# GEVCU-4_2.net
KiCad netlist of a schematic drawn in EAGLE
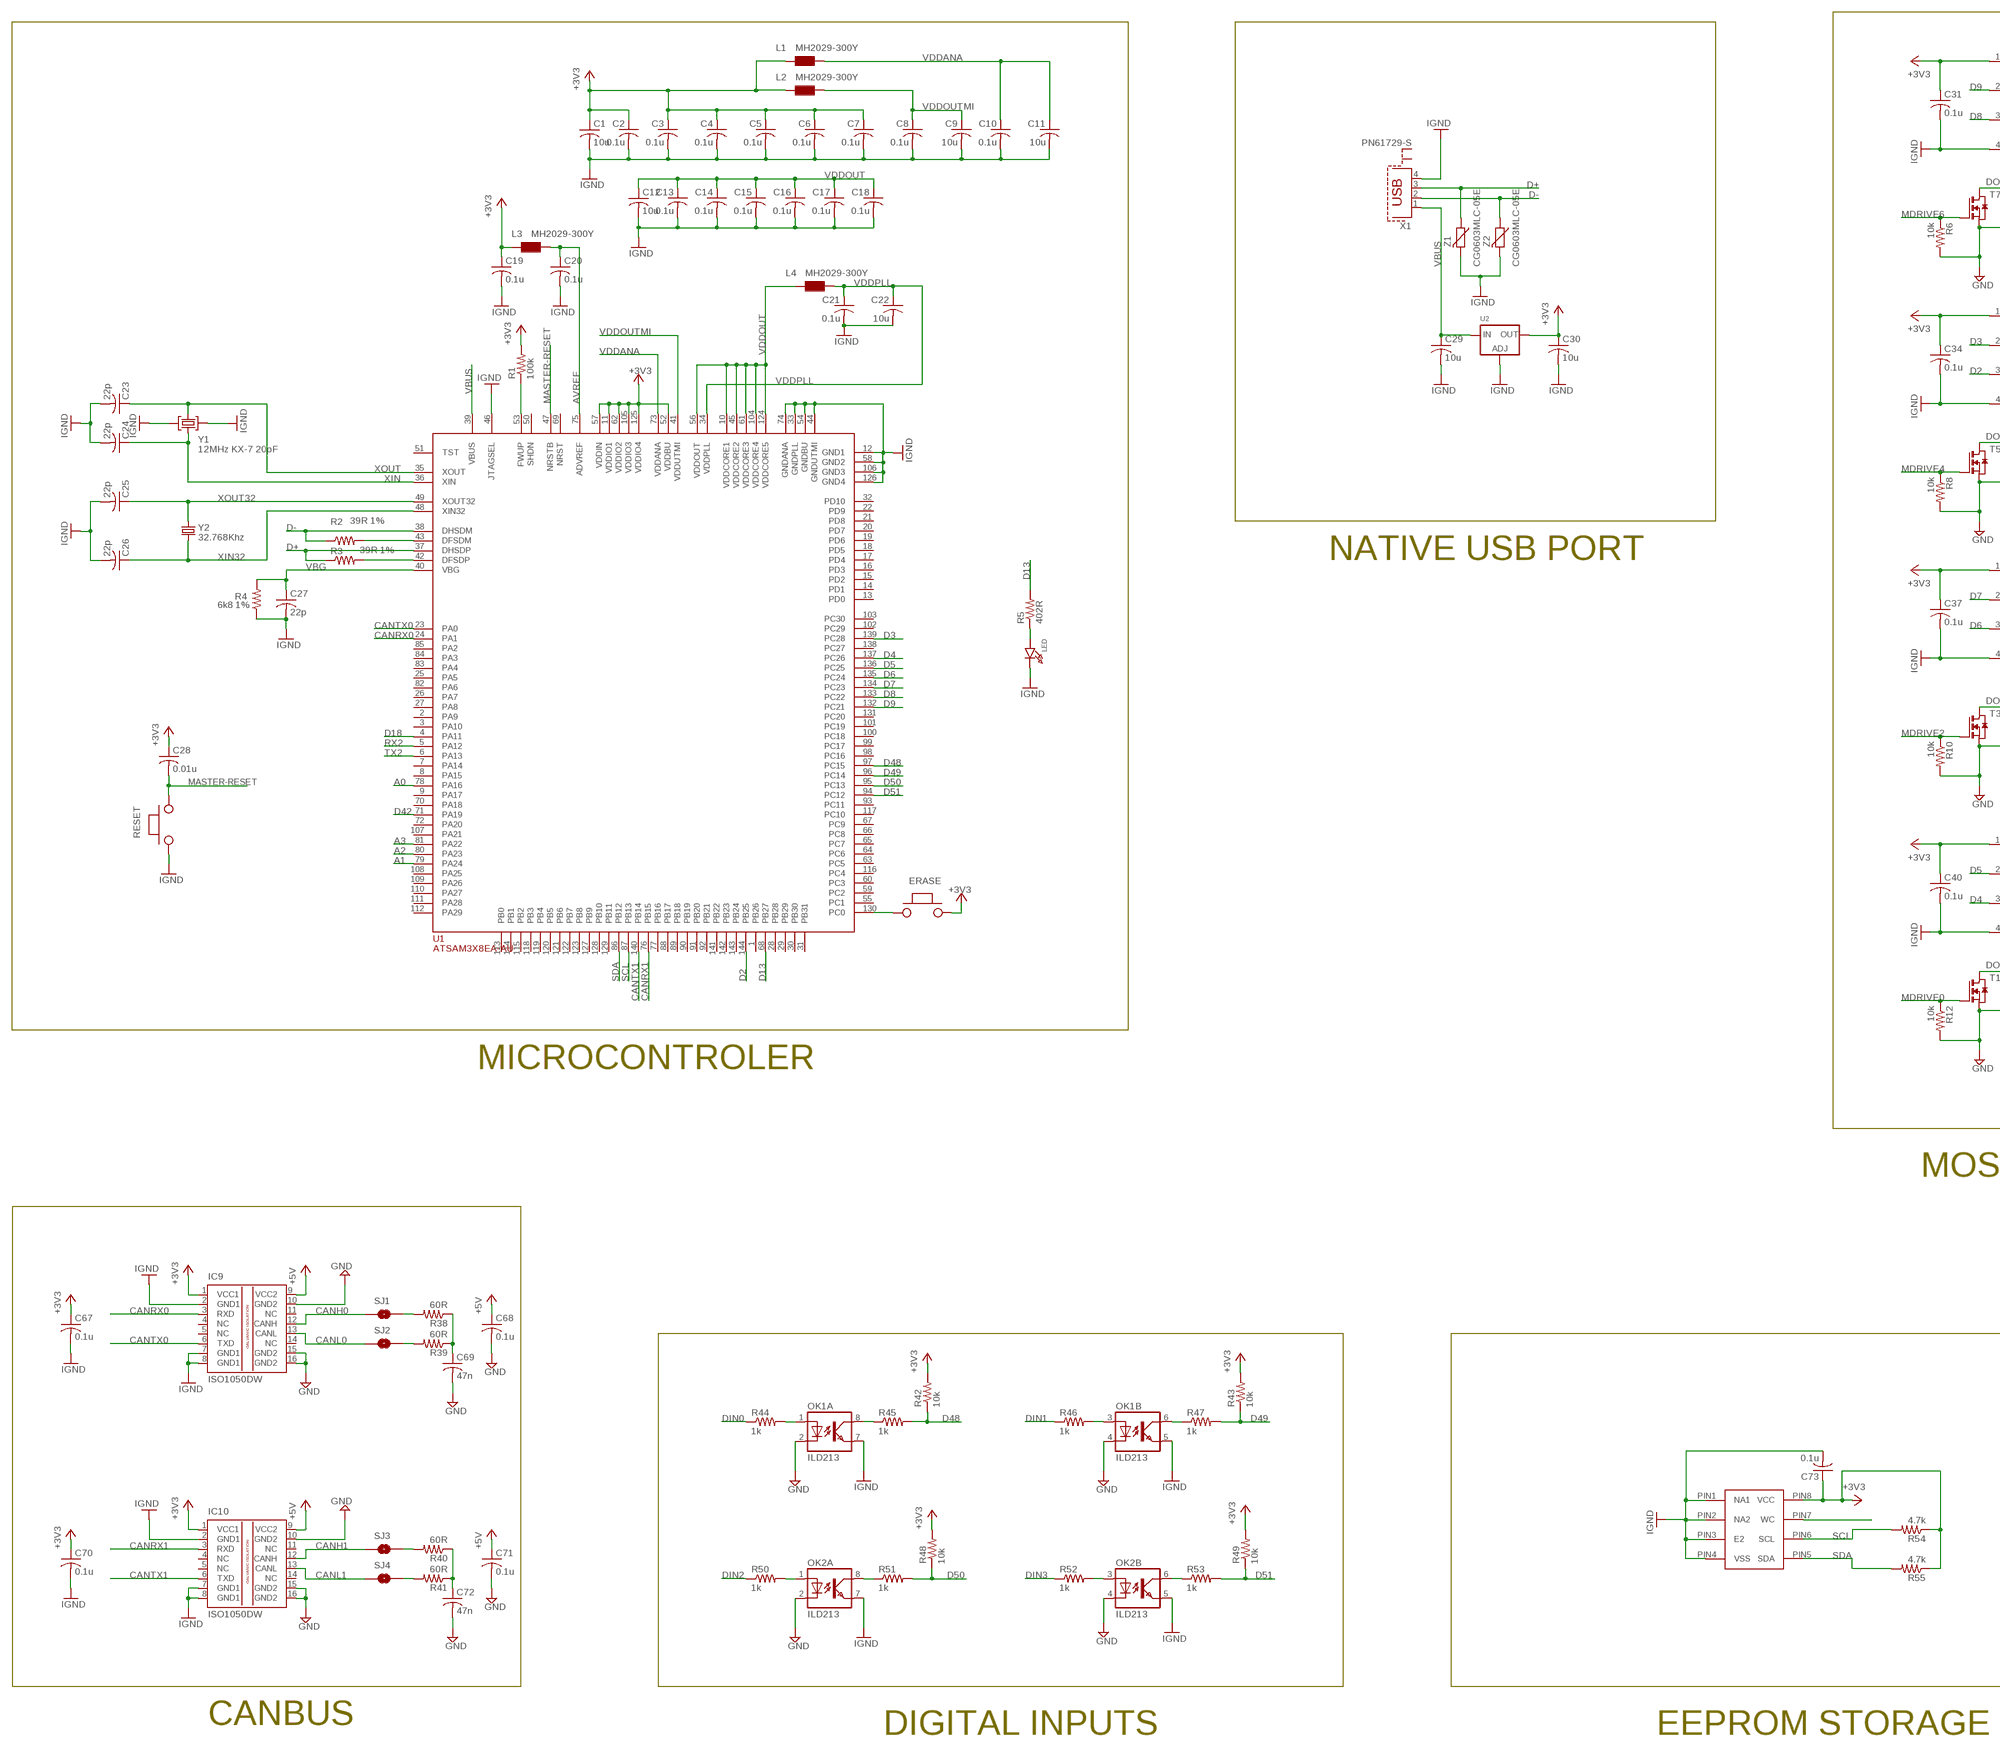
[diagram p0: schematic, sheet 1, part 1 of 2]
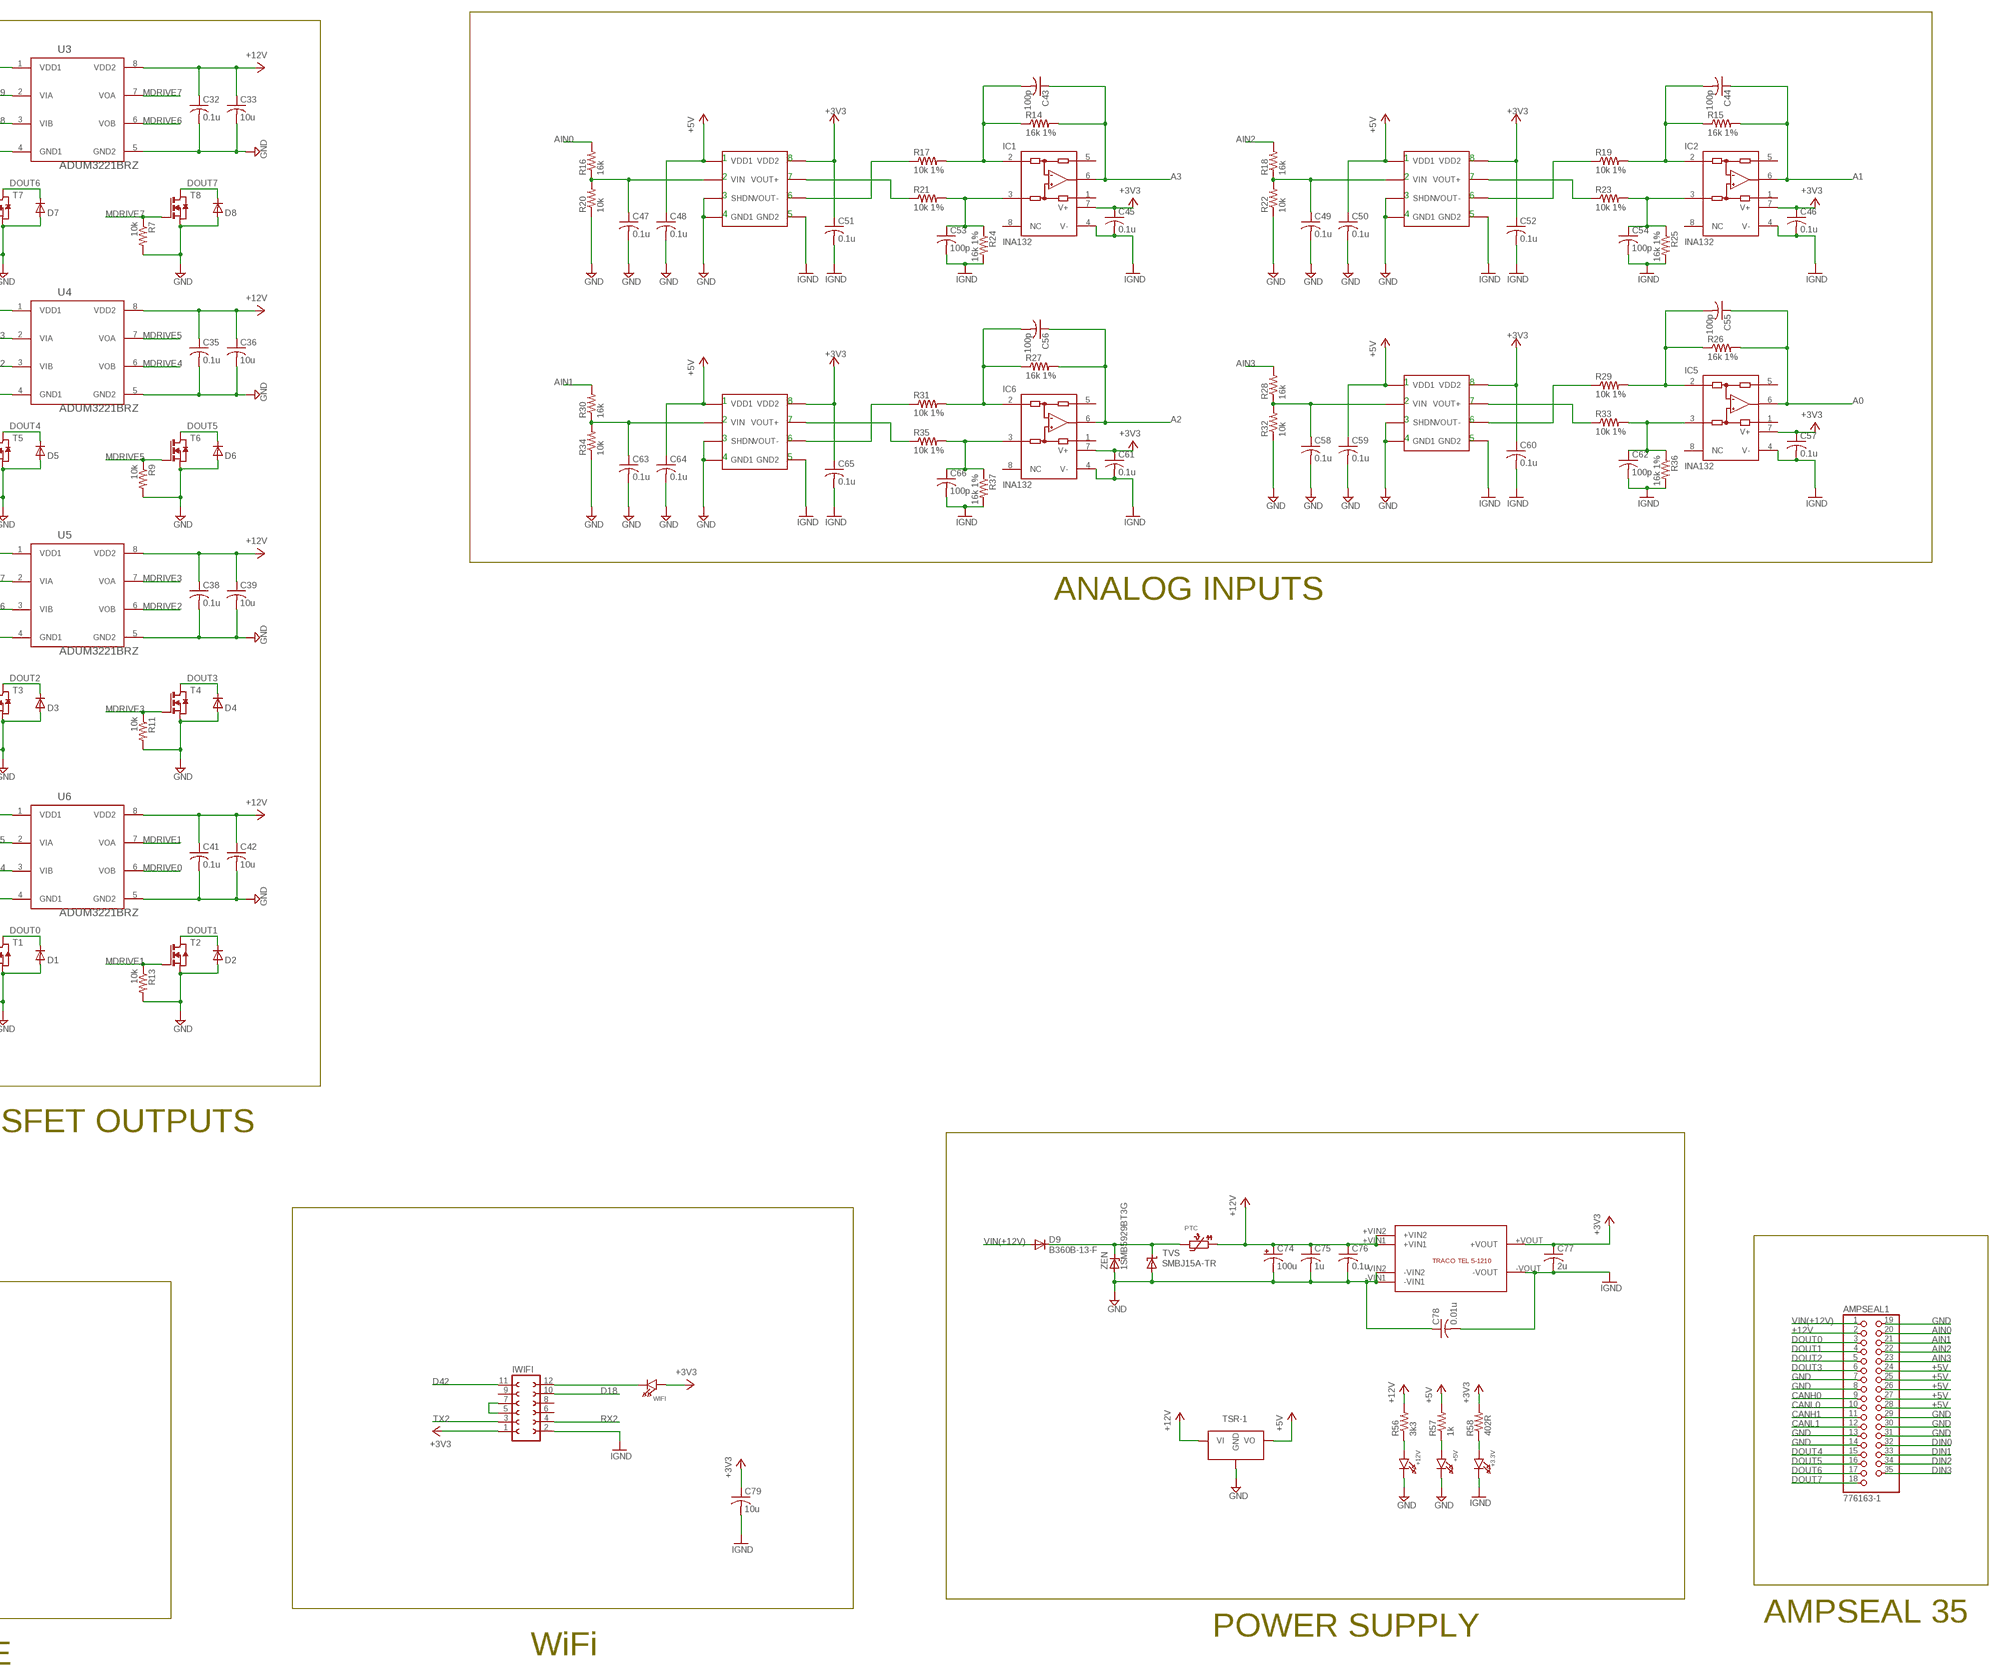
[diagram p1: schematic, sheet 1, part 2 of 2]

(export (version "E")
  (design (tool "Eeschema 10.0.6"))
  (components
    (comp (ref "+3.3V")
      (value "LED0805")
      (footprint "eagle-import:CHIPLED_0805")
      (libsource (lib "eagle-import") (part "LED0805"))
    )
    (comp (ref "+5V")
      (value "LED0805")
      (footprint "eagle-import:CHIPLED_0805")
      (libsource (lib "eagle-import") (part "LED0805"))
    )
    (comp (ref "+12V")
      (value "LED0805")
      (footprint "eagle-import:CHIPLED_0805")
      (libsource (lib "eagle-import") (part "LED0805"))
    )
    (comp (ref "AMPSEAL1")
      (value "776163-1")
      (footprint "eagle-import:AMPSEAL35")
      (libsource (lib "eagle-import") (part "AMPSEAL35"))
    )
    (comp (ref "C1")
      (value "10u")
      (footprint "eagle-import:C0805")
      (libsource (lib "eagle-import") (part "C-USC0805"))
    )
    (comp (ref "C2")
      (value "0.1u")
      (footprint "eagle-import:C0805")
      (libsource (lib "eagle-import") (part "C-USC0805"))
    )
    (comp (ref "C3")
      (value "0.1u")
      (footprint "eagle-import:C0805")
      (libsource (lib "eagle-import") (part "C-USC0805"))
    )
    (comp (ref "C4")
      (value "0.1u")
      (footprint "eagle-import:C0805")
      (libsource (lib "eagle-import") (part "C-USC0805"))
    )
    (comp (ref "C5")
      (value "0.1u")
      (footprint "eagle-import:C0805")
      (libsource (lib "eagle-import") (part "C-USC0805"))
    )
    (comp (ref "C6")
      (value "0.1u")
      (footprint "eagle-import:C0805")
      (libsource (lib "eagle-import") (part "C-USC0805"))
    )
    (comp (ref "C7")
      (value "0.1u")
      (footprint "eagle-import:C0805")
      (libsource (lib "eagle-import") (part "C-USC0805"))
    )
    (comp (ref "C8")
      (value "0.1u")
      (footprint "eagle-import:C0805")
      (libsource (lib "eagle-import") (part "C-USC0805"))
    )
    (comp (ref "C9")
      (value "10u")
      (footprint "eagle-import:C0805")
      (libsource (lib "eagle-import") (part "C-USC0805"))
    )
    (comp (ref "C10")
      (value "0.1u")
      (footprint "eagle-import:C0805")
      (libsource (lib "eagle-import") (part "C-USC0805"))
    )
    (comp (ref "C11")
      (value "10u")
      (footprint "eagle-import:C0805")
      (libsource (lib "eagle-import") (part "C-USC0805"))
    )
    (comp (ref "C12")
      (value "10u")
      (footprint "eagle-import:C0805")
      (libsource (lib "eagle-import") (part "C-USC0805"))
    )
    (comp (ref "C13")
      (value "0.1u")
      (footprint "eagle-import:C0805")
      (libsource (lib "eagle-import") (part "C-USC0805"))
    )
    (comp (ref "C14")
      (value "0.1u")
      (footprint "eagle-import:C0805")
      (libsource (lib "eagle-import") (part "C-USC0805"))
    )
    (comp (ref "C15")
      (value "0.1u")
      (footprint "eagle-import:C0805")
      (libsource (lib "eagle-import") (part "C-USC0805"))
    )
    (comp (ref "C16")
      (value "0.1u")
      (footprint "eagle-import:C0805")
      (libsource (lib "eagle-import") (part "C-USC0805"))
    )
    (comp (ref "C17")
      (value "0.1u")
      (footprint "eagle-import:C0805")
      (libsource (lib "eagle-import") (part "C-USC0805"))
    )
    (comp (ref "C18")
      (value "0.1u")
      (footprint "eagle-import:C0805")
      (libsource (lib "eagle-import") (part "C-USC0805"))
    )
    (comp (ref "C19")
      (value "0.1u")
      (footprint "eagle-import:C0805")
      (libsource (lib "eagle-import") (part "C-USC0805"))
    )
    (comp (ref "C20")
      (value "0.1u")
      (footprint "eagle-import:C0805")
      (libsource (lib "eagle-import") (part "C-USC0805"))
    )
    (comp (ref "C21")
      (value "0.1u")
      (footprint "eagle-import:C0805")
      (libsource (lib "eagle-import") (part "C-USC0805"))
    )
    (comp (ref "C22")
      (value "10u")
      (footprint "eagle-import:C0805")
      (libsource (lib "eagle-import") (part "C-USC0805"))
    )
    (comp (ref "C23")
      (value "22p")
      (footprint "eagle-import:C1206")
      (libsource (lib "eagle-import") (part "C-USC1206"))
    )
    (comp (ref "C24")
      (value "22p")
      (footprint "eagle-import:C1206")
      (libsource (lib "eagle-import") (part "C-USC1206"))
    )
    (comp (ref "C25")
      (value "22p")
      (footprint "eagle-import:C0805")
      (libsource (lib "eagle-import") (part "C-USC0805"))
    )
    (comp (ref "C26")
      (value "22p")
      (footprint "eagle-import:C0805")
      (libsource (lib "eagle-import") (part "C-USC0805"))
    )
    (comp (ref "C27")
      (value "22p")
      (footprint "eagle-import:C0805")
      (libsource (lib "eagle-import") (part "C-USC0805"))
    )
    (comp (ref "C28")
      (value "0.01u")
      (footprint "eagle-import:C0805")
      (libsource (lib "eagle-import") (part "C-USC0805"))
    )
    (comp (ref "C29")
      (value "10u")
      (footprint "eagle-import:C0805")
      (libsource (lib "eagle-import") (part "C-USC0805"))
    )
    (comp (ref "C30")
      (value "10u")
      (footprint "eagle-import:C0805")
      (libsource (lib "eagle-import") (part "C-USC0805"))
    )
    (comp (ref "C31")
      (value "0.1u")
      (footprint "eagle-import:C0805")
      (libsource (lib "eagle-import") (part "C-USC0805"))
    )
    (comp (ref "C32")
      (value "0.1u")
      (footprint "eagle-import:C0805")
      (libsource (lib "eagle-import") (part "C-USC0805"))
    )
    (comp (ref "C33")
      (value "10u")
      (footprint "eagle-import:C0805")
      (libsource (lib "eagle-import") (part "C-USC0805"))
    )
    (comp (ref "C34")
      (value "0.1u")
      (footprint "eagle-import:C0805")
      (libsource (lib "eagle-import") (part "C-USC0805"))
    )
    (comp (ref "C35")
      (value "0.1u")
      (footprint "eagle-import:C0805")
      (libsource (lib "eagle-import") (part "C-USC0805"))
    )
    (comp (ref "C36")
      (value "10u")
      (footprint "eagle-import:C0805")
      (libsource (lib "eagle-import") (part "C-USC0805"))
    )
    (comp (ref "C37")
      (value "0.1u")
      (footprint "eagle-import:C0805")
      (libsource (lib "eagle-import") (part "C-USC0805"))
    )
    (comp (ref "C38")
      (value "0.1u")
      (footprint "eagle-import:C0805")
      (libsource (lib "eagle-import") (part "C-USC0805"))
    )
    (comp (ref "C39")
      (value "10u")
      (footprint "eagle-import:C0805")
      (libsource (lib "eagle-import") (part "C-USC0805"))
    )
    (comp (ref "C40")
      (value "0.1u")
      (footprint "eagle-import:C0805")
      (libsource (lib "eagle-import") (part "C-USC0805"))
    )
    (comp (ref "C41")
      (value "0.1u")
      (footprint "eagle-import:C0805")
      (libsource (lib "eagle-import") (part "C-USC0805"))
    )
    (comp (ref "C42")
      (value "10u")
      (footprint "eagle-import:C0805")
      (libsource (lib "eagle-import") (part "C-USC0805"))
    )
    (comp (ref "C43")
      (value "100p")
      (footprint "eagle-import:C0805")
      (libsource (lib "eagle-import") (part "C-USC0805"))
    )
    (comp (ref "C44")
      (value "100p")
      (footprint "eagle-import:C0805")
      (libsource (lib "eagle-import") (part "C-USC0805"))
    )
    (comp (ref "C45")
      (value "0.1u")
      (footprint "eagle-import:C0805")
      (libsource (lib "eagle-import") (part "C-USC0805"))
    )
    (comp (ref "C46")
      (value "0.1u")
      (footprint "eagle-import:C0805")
      (libsource (lib "eagle-import") (part "C-USC0805"))
    )
    (comp (ref "C47")
      (value "0.1u")
      (footprint "eagle-import:C0805")
      (libsource (lib "eagle-import") (part "C-USC0805"))
    )
    (comp (ref "C48")
      (value "0.1u")
      (footprint "eagle-import:C1206")
      (libsource (lib "eagle-import") (part "C-USC1206"))
    )
    (comp (ref "C49")
      (value "0.1u")
      (footprint "eagle-import:C0805")
      (libsource (lib "eagle-import") (part "C-USC0805"))
    )
    (comp (ref "C50")
      (value "0.1u")
      (footprint "eagle-import:C1206")
      (libsource (lib "eagle-import") (part "C-USC1206"))
    )
    (comp (ref "C51")
      (value "0.1u")
      (footprint "eagle-import:C0805")
      (libsource (lib "eagle-import") (part "C-USC0805"))
    )
    (comp (ref "C52")
      (value "0.1u")
      (footprint "eagle-import:C0805")
      (libsource (lib "eagle-import") (part "C-USC0805"))
    )
    (comp (ref "C53")
      (value "100p")
      (footprint "eagle-import:C0805")
      (libsource (lib "eagle-import") (part "C-USC0805"))
    )
    (comp (ref "C54")
      (value "100p")
      (footprint "eagle-import:C0805")
      (libsource (lib "eagle-import") (part "C-USC0805"))
    )
    (comp (ref "C55")
      (value "100p")
      (footprint "eagle-import:C0805")
      (libsource (lib "eagle-import") (part "C-USC0805"))
    )
    (comp (ref "C56")
      (value "100p")
      (footprint "eagle-import:C0805")
      (libsource (lib "eagle-import") (part "C-USC0805"))
    )
    (comp (ref "C57")
      (value "0.1u")
      (footprint "eagle-import:C0805")
      (libsource (lib "eagle-import") (part "C-USC0805"))
    )
    (comp (ref "C58")
      (value "0.1u")
      (footprint "eagle-import:C0805")
      (libsource (lib "eagle-import") (part "C-USC0805"))
    )
    (comp (ref "C59")
      (value "0.1u")
      (footprint "eagle-import:C1206")
      (libsource (lib "eagle-import") (part "C-USC1206"))
    )
    (comp (ref "C60")
      (value "0.1u")
      (footprint "eagle-import:C0805")
      (libsource (lib "eagle-import") (part "C-USC0805"))
    )
    (comp (ref "C61")
      (value "0.1u")
      (footprint "eagle-import:C0805")
      (libsource (lib "eagle-import") (part "C-USC0805"))
    )
    (comp (ref "C62")
      (value "100p")
      (footprint "eagle-import:C0805")
      (libsource (lib "eagle-import") (part "C-USC0805"))
    )
    (comp (ref "C63")
      (value "0.1u")
      (footprint "eagle-import:C0805")
      (libsource (lib "eagle-import") (part "C-USC0805"))
    )
    (comp (ref "C64")
      (value "0.1u")
      (footprint "eagle-import:C1206")
      (libsource (lib "eagle-import") (part "C-USC1206"))
    )
    (comp (ref "C65")
      (value "0.1u")
      (footprint "eagle-import:C0805")
      (libsource (lib "eagle-import") (part "C-USC0805"))
    )
    (comp (ref "C66")
      (value "100p")
      (footprint "eagle-import:C0805")
      (libsource (lib "eagle-import") (part "C-USC0805"))
    )
    (comp (ref "C67")
      (value "0.1u")
      (footprint "eagle-import:C0805")
      (libsource (lib "eagle-import") (part "C-USC0805"))
    )
    (comp (ref "C68")
      (value "0.1u")
      (footprint "eagle-import:C0805")
      (libsource (lib "eagle-import") (part "C-USC0805"))
    )
    (comp (ref "C69")
      (value "47n")
      (footprint "eagle-import:C0805")
      (libsource (lib "eagle-import") (part "C-USC0805"))
    )
    (comp (ref "C70")
      (value "0.1u")
      (footprint "eagle-import:C0805")
      (libsource (lib "eagle-import") (part "C-USC0805"))
    )
    (comp (ref "C71")
      (value "0.1u")
      (footprint "eagle-import:C0805")
      (libsource (lib "eagle-import") (part "C-USC0805"))
    )
    (comp (ref "C72")
      (value "47n")
      (footprint "eagle-import:C0805")
      (libsource (lib "eagle-import") (part "C-USC0805"))
    )
    (comp (ref "C73")
      (value "0.1u")
      (footprint "eagle-import:C0805")
      (libsource (lib "eagle-import") (part "C-USC0805"))
    )
    (comp (ref "C74")
      (value "100u")
      (footprint "eagle-import:E2,5-6")
      (libsource (lib "eagle-import") (part "CPOL-USE2.5-6"))
    )
    (comp (ref "C75")
      (value "1u")
      (footprint "eagle-import:C0805")
      (libsource (lib "eagle-import") (part "C-USC0805"))
    )
    (comp (ref "C76")
      (value "0.1u")
      (footprint "eagle-import:C0805")
      (libsource (lib "eagle-import") (part "C-USC0805"))
    )
    (comp (ref "C77")
      (value "2u")
      (footprint "eagle-import:C0805")
      (libsource (lib "eagle-import") (part "C-USC0805"))
    )
    (comp (ref "C78")
      (value "0.01u")
      (footprint "eagle-import:C1812")
      (libsource (lib "eagle-import") (part "C-USC1812"))
    )
    (comp (ref "C79")
      (value "10u")
      (footprint "eagle-import:C0805")
      (libsource (lib "eagle-import") (part "C-USC0805"))
    )
    (comp (ref "D1")
      (value "MBR0520LT")
      (footprint "eagle-import:SOD123")
      (libsource (lib "eagle-import") (part "MBR0520LT"))
    )
    (comp (ref "D2")
      (value "MBR0520LT")
      (footprint "eagle-import:SOD123")
      (libsource (lib "eagle-import") (part "MBR0520LT"))
    )
    (comp (ref "D3")
      (value "MBR0520LT")
      (footprint "eagle-import:SOD123")
      (libsource (lib "eagle-import") (part "MBR0520LT"))
    )
    (comp (ref "D4")
      (value "MBR0520LT")
      (footprint "eagle-import:SOD123")
      (libsource (lib "eagle-import") (part "MBR0520LT"))
    )
    (comp (ref "D5")
      (value "MBR0520LT")
      (footprint "eagle-import:SOD123")
      (libsource (lib "eagle-import") (part "MBR0520LT"))
    )
    (comp (ref "D6")
      (value "MBR0520LT")
      (footprint "eagle-import:SOD123")
      (libsource (lib "eagle-import") (part "MBR0520LT"))
    )
    (comp (ref "D7")
      (value "MBR0520LT")
      (footprint "eagle-import:SOD123")
      (libsource (lib "eagle-import") (part "MBR0520LT"))
    )
    (comp (ref "D8")
      (value "MBR0520LT")
      (footprint "eagle-import:SOD123")
      (libsource (lib "eagle-import") (part "MBR0520LT"))
    )
    (comp (ref "D9")
      (value "B360B-13-F")
      (footprint "eagle-import:SMB")
      (libsource (lib "eagle-import") (part "DIODE-SMB"))
    )
    (comp (ref "ERASE")
      (value "PUCHBUTTON")
      (footprint "eagle-import:PUCHBUTTON")
      (libsource (lib "eagle-import") (part "PUCHBUTTON"))
    )
    (comp (ref "IC1")
      (value "INA132")
      (footprint "eagle-import:SO08")
      (fields (field (name "MF") "TEXAS INSTRUMENTS") (field (name "MPN") "INA105KU"))
      (libsource (lib "eagle-import") (part "INA105U"))
    )
    (comp (ref "IC2")
      (value "INA132")
      (footprint "eagle-import:SO08")
      (fields (field (name "MF") "TEXAS INSTRUMENTS") (field (name "MPN") "INA105KU"))
      (libsource (lib "eagle-import") (part "INA105U"))
    )
    (comp (ref "IC3")
      (value "CK_CUSTOM_ACPL-C87A-000E")
      (footprint "eagle-import:CK_CUSTOM_SO8-WIDE")
      (libsource (lib "eagle-import") (part "CK_CUSTOM_ACPL-C87A-000E"))
    )
    (comp (ref "IC4")
      (value "CK_CUSTOM_ACPL-C87A-000E")
      (footprint "eagle-import:CK_CUSTOM_SO8-WIDE")
      (libsource (lib "eagle-import") (part "CK_CUSTOM_ACPL-C87A-000E"))
    )
    (comp (ref "IC5")
      (value "INA132")
      (footprint "eagle-import:SO08")
      (fields (field (name "MF") "TEXAS INSTRUMENTS") (field (name "MPN") "INA105KU"))
      (libsource (lib "eagle-import") (part "INA105U"))
    )
    (comp (ref "IC6")
      (value "INA132")
      (footprint "eagle-import:SO08")
      (fields (field (name "MF") "TEXAS INSTRUMENTS") (field (name "MPN") "INA105KU"))
      (libsource (lib "eagle-import") (part "INA105U"))
    )
    (comp (ref "IC7")
      (value "CK_CUSTOM_ACPL-C87A-000E")
      (footprint "eagle-import:CK_CUSTOM_SO8-WIDE")
      (libsource (lib "eagle-import") (part "CK_CUSTOM_ACPL-C87A-000E"))
    )
    (comp (ref "IC8")
      (value "CK_CUSTOM_ACPL-C87A-000E")
      (footprint "eagle-import:CK_CUSTOM_SO8-WIDE")
      (libsource (lib "eagle-import") (part "CK_CUSTOM_ACPL-C87A-000E"))
    )
    (comp (ref "IC9")
      (value "ISO1050DW")
      (footprint "eagle-import:DUB-R-PDSO-G8")
      (libsource (lib "eagle-import") (part "ISO1050DUB"))
    )
    (comp (ref "IC10")
      (value "ISO1050DW")
      (footprint "eagle-import:DUB-R-PDSO-G8")
      (libsource (lib "eagle-import") (part "ISO1050DUB"))
    )
    (comp (ref "IWIFI")
      (value "FE06-2")
      (footprint "eagle-import:FE06-2")
      (libsource (lib "eagle-import") (part "FE06-2"))
    )
    (comp (ref "L1")
      (value "MH2029-300Y")
      (footprint "eagle-import:0805")
      (libsource (lib "eagle-import") (part "WE-CBF_0805"))
    )
    (comp (ref "L2")
      (value "MH2029-300Y")
      (footprint "eagle-import:0805")
      (libsource (lib "eagle-import") (part "WE-CBF_0805"))
    )
    (comp (ref "L3")
      (value "MH2029-300Y")
      (footprint "eagle-import:0805")
      (libsource (lib "eagle-import") (part "WE-CBF_0805"))
    )
    (comp (ref "L4")
      (value "MH2029-300Y")
      (footprint "eagle-import:0805")
      (libsource (lib "eagle-import") (part "WE-CBF_0805"))
    )
    (comp (ref "LED")
      (value "LED0805")
      (footprint "eagle-import:CHIPLED_0805")
      (libsource (lib "eagle-import") (part "LED0805"))
    )
    (comp (ref "OK1")
      (value "ILD213")
      (footprint "eagle-import:SOIC08")
      (fields (field (name "MF") "VISHAY/TELEFUNKEN") (field (name "MPN") "ILD213T"))
      (libsource (lib "eagle-import") (part "ILD213"))
    )
    (comp (ref "OK2")
      (value "ILD213")
      (footprint "eagle-import:SOIC08")
      (fields (field (name "MF") "VISHAY/TELEFUNKEN") (field (name "MPN") "ILD213T"))
      (libsource (lib "eagle-import") (part "ILD213"))
    )
    (comp (ref "PTC")
      (value "PTC1812")
      (footprint "eagle-import:PTC1812")
      (libsource (lib "eagle-import") (part "PTC1812"))
    )
    (comp (ref "R1")
      (value "100k")
      (footprint "eagle-import:R0805")
      (libsource (lib "eagle-import") (part "R-US_R0805"))
    )
    (comp (ref "R2")
      (value "39R 1%")
      (footprint "eagle-import:R0805")
      (libsource (lib "eagle-import") (part "R-US_R0805"))
    )
    (comp (ref "R3")
      (value "39R 1%")
      (footprint "eagle-import:R0805")
      (libsource (lib "eagle-import") (part "R-US_R0805"))
    )
    (comp (ref "R4")
      (value "6k8 1%")
      (footprint "eagle-import:R0805")
      (libsource (lib "eagle-import") (part "R-US_R0805"))
    )
    (comp (ref "R5")
      (value "402R")
      (footprint "eagle-import:R0805")
      (libsource (lib "eagle-import") (part "R-US_R0805"))
    )
    (comp (ref "R6")
      (value "10k")
      (footprint "eagle-import:R0805")
      (libsource (lib "eagle-import") (part "R-US_R0805"))
    )
    (comp (ref "R7")
      (value "10k")
      (footprint "eagle-import:R0805")
      (libsource (lib "eagle-import") (part "R-US_R0805"))
    )
    (comp (ref "R8")
      (value "10k")
      (footprint "eagle-import:R0805")
      (libsource (lib "eagle-import") (part "R-US_R0805"))
    )
    (comp (ref "R9")
      (value "10k")
      (footprint "eagle-import:R0805")
      (libsource (lib "eagle-import") (part "R-US_R0805"))
    )
    (comp (ref "R10")
      (value "10k")
      (footprint "eagle-import:R0805")
      (libsource (lib "eagle-import") (part "R-US_R0805"))
    )
    (comp (ref "R11")
      (value "10k")
      (footprint "eagle-import:R0805")
      (libsource (lib "eagle-import") (part "R-US_R0805"))
    )
    (comp (ref "R12")
      (value "10k")
      (footprint "eagle-import:R0805")
      (libsource (lib "eagle-import") (part "R-US_R0805"))
    )
    (comp (ref "R13")
      (value "10k")
      (footprint "eagle-import:R0805")
      (libsource (lib "eagle-import") (part "R-US_R0805"))
    )
    (comp (ref "R14")
      (value "16k 1%")
      (footprint "eagle-import:R0805")
      (libsource (lib "eagle-import") (part "R-US_R0805"))
    )
    (comp (ref "R15")
      (value "16k 1%")
      (footprint "eagle-import:R0805")
      (libsource (lib "eagle-import") (part "R-US_R0805"))
    )
    (comp (ref "R16")
      (value "16k")
      (footprint "eagle-import:R0805")
      (libsource (lib "eagle-import") (part "R-US_R0805"))
    )
    (comp (ref "R17")
      (value "10k 1%")
      (footprint "eagle-import:R0805")
      (libsource (lib "eagle-import") (part "R-US_R0805"))
    )
    (comp (ref "R18")
      (value "16k")
      (footprint "eagle-import:R0805")
      (libsource (lib "eagle-import") (part "R-US_R0805"))
    )
    (comp (ref "R19")
      (value "10k 1%")
      (footprint "eagle-import:R0805")
      (libsource (lib "eagle-import") (part "R-US_R0805"))
    )
    (comp (ref "R20")
      (value "10k")
      (footprint "eagle-import:R0805")
      (libsource (lib "eagle-import") (part "R-US_R0805"))
    )
    (comp (ref "R21")
      (value "10k 1%")
      (footprint "eagle-import:R0805")
      (libsource (lib "eagle-import") (part "R-US_R0805"))
    )
    (comp (ref "R22")
      (value "10k")
      (footprint "eagle-import:R0805")
      (libsource (lib "eagle-import") (part "R-US_R0805"))
    )
    (comp (ref "R23")
      (value "10k 1%")
      (footprint "eagle-import:R0805")
      (libsource (lib "eagle-import") (part "R-US_R0805"))
    )
    (comp (ref "R24")
      (value "16k 1%")
      (footprint "eagle-import:R0805")
      (libsource (lib "eagle-import") (part "R-US_R0805"))
    )
    (comp (ref "R25")
      (value "16k 1%")
      (footprint "eagle-import:R0805")
      (libsource (lib "eagle-import") (part "R-US_R0805"))
    )
    (comp (ref "R26")
      (value "16k 1%")
      (footprint "eagle-import:R0805")
      (libsource (lib "eagle-import") (part "R-US_R0805"))
    )
    (comp (ref "R27")
      (value "16k 1%")
      (footprint "eagle-import:R0805")
      (libsource (lib "eagle-import") (part "R-US_R0805"))
    )
    (comp (ref "R28")
      (value "16k")
      (footprint "eagle-import:R0805")
      (libsource (lib "eagle-import") (part "R-US_R0805"))
    )
    (comp (ref "R29")
      (value "10k 1%")
      (footprint "eagle-import:R0805")
      (libsource (lib "eagle-import") (part "R-US_R0805"))
    )
    (comp (ref "R30")
      (value "16k")
      (footprint "eagle-import:R0805")
      (libsource (lib "eagle-import") (part "R-US_R0805"))
    )
    (comp (ref "R31")
      (value "10k 1%")
      (footprint "eagle-import:R0805")
      (libsource (lib "eagle-import") (part "R-US_R0805"))
    )
    (comp (ref "R32")
      (value "10k")
      (footprint "eagle-import:R0805")
      (libsource (lib "eagle-import") (part "R-US_R0805"))
    )
    (comp (ref "R33")
      (value "10k 1%")
      (footprint "eagle-import:R0805")
      (libsource (lib "eagle-import") (part "R-US_R0805"))
    )
    (comp (ref "R34")
      (value "10k")
      (footprint "eagle-import:R0805")
      (libsource (lib "eagle-import") (part "R-US_R0805"))
    )
    (comp (ref "R35")
      (value "10k 1%")
      (footprint "eagle-import:R0805")
      (libsource (lib "eagle-import") (part "R-US_R0805"))
    )
    (comp (ref "R36")
      (value "16k 1%")
      (footprint "eagle-import:R0805")
      (libsource (lib "eagle-import") (part "R-US_R0805"))
    )
    (comp (ref "R37")
      (value "16k 1%")
      (footprint "eagle-import:R0805")
      (libsource (lib "eagle-import") (part "R-US_R0805"))
    )
    (comp (ref "R38")
      (value "60R")
      (footprint "eagle-import:R0805")
      (libsource (lib "eagle-import") (part "R-US_R0805"))
    )
    (comp (ref "R39")
      (value "60R")
      (footprint "eagle-import:R0805")
      (libsource (lib "eagle-import") (part "R-US_R0805"))
    )
    (comp (ref "R40")
      (value "60R")
      (footprint "eagle-import:R0805")
      (libsource (lib "eagle-import") (part "R-US_R0805"))
    )
    (comp (ref "R41")
      (value "60R")
      (footprint "eagle-import:R0805")
      (libsource (lib "eagle-import") (part "R-US_R0805"))
    )
    (comp (ref "R42")
      (value "10k")
      (footprint "eagle-import:R0805")
      (libsource (lib "eagle-import") (part "R-US_R0805"))
    )
    (comp (ref "R43")
      (value "10k")
      (footprint "eagle-import:R0805")
      (libsource (lib "eagle-import") (part "R-US_R0805"))
    )
    (comp (ref "R44")
      (value "1k")
      (footprint "eagle-import:R0805")
      (libsource (lib "eagle-import") (part "R-US_R0805"))
    )
    (comp (ref "R45")
      (value "1k")
      (footprint "eagle-import:R0805")
      (libsource (lib "eagle-import") (part "R-US_R0805"))
    )
    (comp (ref "R46")
      (value "1k")
      (footprint "eagle-import:R0805")
      (libsource (lib "eagle-import") (part "R-US_R0805"))
    )
    (comp (ref "R47")
      (value "1k")
      (footprint "eagle-import:R0805")
      (libsource (lib "eagle-import") (part "R-US_R0805"))
    )
    (comp (ref "R48")
      (value "10k")
      (footprint "eagle-import:R0805")
      (libsource (lib "eagle-import") (part "R-US_R0805"))
    )
    (comp (ref "R49")
      (value "10k")
      (footprint "eagle-import:R0805")
      (libsource (lib "eagle-import") (part "R-US_R0805"))
    )
    (comp (ref "R50")
      (value "1k")
      (footprint "eagle-import:R0805")
      (libsource (lib "eagle-import") (part "R-US_R0805"))
    )
    (comp (ref "R51")
      (value "1k")
      (footprint "eagle-import:R0805")
      (libsource (lib "eagle-import") (part "R-US_R0805"))
    )
    (comp (ref "R52")
      (value "1k")
      (footprint "eagle-import:R0805")
      (libsource (lib "eagle-import") (part "R-US_R0805"))
    )
    (comp (ref "R53")
      (value "1k")
      (footprint "eagle-import:R0805")
      (libsource (lib "eagle-import") (part "R-US_R0805"))
    )
    (comp (ref "R54")
      (value "4.7k")
      (footprint "eagle-import:R0805")
      (libsource (lib "eagle-import") (part "R-US_R0805"))
    )
    (comp (ref "R55")
      (value "4.7k")
      (footprint "eagle-import:R0805")
      (libsource (lib "eagle-import") (part "R-US_R0805"))
    )
    (comp (ref "R56")
      (value "3k3")
      (footprint "eagle-import:R0805")
      (libsource (lib "eagle-import") (part "R-US_R0805"))
    )
    (comp (ref "R57")
      (value "1k")
      (footprint "eagle-import:R0805")
      (libsource (lib "eagle-import") (part "R-US_R0805"))
    )
    (comp (ref "R58")
      (value "402R")
      (footprint "eagle-import:R0805")
      (libsource (lib "eagle-import") (part "R-US_R0805"))
    )
    (comp (ref "RESET")
      (value "PUCHBUTTON")
      (footprint "eagle-import:PUCHBUTTON")
      (libsource (lib "eagle-import") (part "PUCHBUTTON"))
    )
    (comp (ref "SJ1")
      (value "SOLDERJUMPERNO")
      (footprint "eagle-import:SJ_2S-NO")
      (libsource (lib "eagle-import") (part "SOLDERJUMPERNO"))
    )
    (comp (ref "SJ2")
      (value "SOLDERJUMPERNO")
      (footprint "eagle-import:SJ_2S-NO")
      (libsource (lib "eagle-import") (part "SOLDERJUMPERNO"))
    )
    (comp (ref "SJ3")
      (value "SOLDERJUMPERNO")
      (footprint "eagle-import:SJ_2S-NO")
      (libsource (lib "eagle-import") (part "SOLDERJUMPERNO"))
    )
    (comp (ref "SJ4")
      (value "SOLDERJUMPERNO")
      (footprint "eagle-import:SJ_2S-NO")
      (libsource (lib "eagle-import") (part "SOLDERJUMPERNO"))
    )
    (comp (ref "T1")
      (value "NMOSSOT223")
      (footprint "eagle-import:SOT223")
      (libsource (lib "eagle-import") (part "NMOSSOT223"))
    )
    (comp (ref "T2")
      (value "NMOSSOT223")
      (footprint "eagle-import:SOT223")
      (libsource (lib "eagle-import") (part "NMOSSOT223"))
    )
    (comp (ref "T3")
      (value "NMOSSOT223")
      (footprint "eagle-import:SOT223")
      (libsource (lib "eagle-import") (part "NMOSSOT223"))
    )
    (comp (ref "T4")
      (value "NMOSSOT223")
      (footprint "eagle-import:SOT223")
      (libsource (lib "eagle-import") (part "NMOSSOT223"))
    )
    (comp (ref "T5")
      (value "NMOSSOT223")
      (footprint "eagle-import:SOT223")
      (libsource (lib "eagle-import") (part "NMOSSOT223"))
    )
    (comp (ref "T6")
      (value "NMOSSOT223")
      (footprint "eagle-import:SOT223")
      (libsource (lib "eagle-import") (part "NMOSSOT223"))
    )
    (comp (ref "T7")
      (value "NMOSSOT223")
      (footprint "eagle-import:SOT223")
      (libsource (lib "eagle-import") (part "NMOSSOT223"))
    )
    (comp (ref "T8")
      (value "NMOSSOT223")
      (footprint "eagle-import:SOT223")
      (libsource (lib "eagle-import") (part "NMOSSOT223"))
    )
    (comp (ref "TVS")
      (value "SMBJ15A-TR")
      (footprint "eagle-import:SMBJ")
      (libsource (lib "eagle-import") (part "SUPPRESSOR-SMBJ"))
    )
    (comp (ref "U1")
      (value "ATSAM3X8EA-AU")
      (footprint "eagle-import:LQFP144")
      (libsource (lib "eagle-import") (part "ATSAM3X/AAU"))
    )
    (comp (ref "U2")
      (value "LM1117SOT223-WAVE")
      (footprint "eagle-import:SOT223-W")
      (libsource (lib "eagle-import") (part "LM1117SOT223-WAVE"))
    )
    (comp (ref "U3")
      (value "ADUM3221BRZ")
      (footprint "eagle-import:SOIC127P600X175-8N")
      (libsource (lib "eagle-import") (part "ADUM3221BRZ"))
    )
    (comp (ref "U4")
      (value "ADUM3221BRZ")
      (footprint "eagle-import:SOIC127P600X175-8N")
      (libsource (lib "eagle-import") (part "ADUM3221BRZ"))
    )
    (comp (ref "U5")
      (value "ADUM3221BRZ")
      (footprint "eagle-import:SOIC127P600X175-8N")
      (libsource (lib "eagle-import") (part "ADUM3221BRZ"))
    )
    (comp (ref "U6")
      (value "ADUM3221BRZ")
      (footprint "eagle-import:SOIC127P600X175-8N")
      (libsource (lib "eagle-import") (part "ADUM3221BRZ"))
    )
    (comp (ref "U7")
      (value "CK_CUSTOM_M24M02-DRMN6TP")
      (footprint "eagle-import:CK_CUSTOM_SOIC8")
      (libsource (lib "eagle-import") (part "CK_CUSTOM_M24M02-DRMN6TP"))
    )
    (comp (ref "U8")
      (value "TRACO")
      (footprint "eagle-import:TRACO")
      (libsource (lib "eagle-import") (part "TRACO"))
    )
    (comp (ref "U9")
      (value "TSR-1")
      (footprint "eagle-import:TSR-1")
      (libsource (lib "eagle-import") (part "TSR-1"))
    )
    (comp (ref "WIFI")
      (value "LED0805")
      (footprint "eagle-import:CHIPLED_0805")
      (libsource (lib "eagle-import") (part "LED0805"))
    )
    (comp (ref "X1")
      (value "PN61729-S")
      (footprint "eagle-import:PN61729-S")
      (libsource (lib "eagle-import") (part "PN61729-S"))
    )
    (comp (ref "Y1")
      (value "12MHz KX-7 20pF")
      (footprint "eagle-import:CRYSTAL-3.2-2.5")
      (libsource (lib "eagle-import") (part "CRYSTAL-3.2-2.5"))
    )
    (comp (ref "Y2")
      (value "32.768Khz")
      (footprint "eagle-import:ARDUINO_WIFI_SHIELD_V018_TG_RESONATOR_EPSON_FC_145")
      (libsource (lib "eagle-import") (part "ARDUINO_WIFI_SHIELD_V018_TG_RESONATOR_EPSON_FC_145"))
    )
    (comp (ref "Z1")
      (value "CG0603MLC-05E")
      (footprint "eagle-import:CT_CN0603")
      (libsource (lib "eagle-import") (part "VARISTORCN0603"))
    )
    (comp (ref "Z2")
      (value "CG0603MLC-05E")
      (footprint "eagle-import:CT_CN0603")
      (libsource (lib "eagle-import") (part "VARISTORCN0603"))
    )
    (comp (ref "ZEN")
      (value "1SMB5929BT3G")
      (footprint "eagle-import:SMB")
      (libsource (lib "eagle-import") (part "ZENER-DIODESMB"))
    )
  )
  (nets
    (net (code "1") (name "+3V3") (class "Default")
      (node (ref "C1") (pin "1") (pinfunction "1_1") (pintype "passive"))
      (node (ref "C19") (pin "1") (pinfunction "1_1") (pintype "passive"))
      (node (ref "C2") (pin "1") (pinfunction "1_1") (pintype "passive"))
      (node (ref "C28") (pin "1") (pinfunction "1_1") (pintype "passive"))
      (node (ref "C3") (pin "1") (pinfunction "1_1") (pintype "passive"))
      (node (ref "C30") (pin "1") (pinfunction "1_1") (pintype "passive"))
      (node (ref "C31") (pin "1") (pinfunction "1_1") (pintype "passive"))
      (node (ref "C34") (pin "1") (pinfunction "1_1") (pintype "passive"))
      (node (ref "C37") (pin "1") (pinfunction "1_1") (pintype "passive"))
      (node (ref "C4") (pin "1") (pinfunction "1_1") (pintype "passive"))
      (node (ref "C40") (pin "1") (pinfunction "1_1") (pintype "passive"))
      (node (ref "C45") (pin "1") (pinfunction "1_1") (pintype "passive"))
      (node (ref "C46") (pin "1") (pinfunction "1_1") (pintype "passive"))
      (node (ref "C5") (pin "1") (pinfunction "1_1") (pintype "passive"))
      (node (ref "C51") (pin "1") (pinfunction "1_1") (pintype "passive"))
      (node (ref "C52") (pin "1") (pinfunction "1_1") (pintype "passive"))
      (node (ref "C57") (pin "1") (pinfunction "1_1") (pintype "passive"))
      (node (ref "C6") (pin "1") (pinfunction "1_1") (pintype "passive"))
      (node (ref "C60") (pin "1") (pinfunction "1_1") (pintype "passive"))
      (node (ref "C61") (pin "1") (pinfunction "1_1") (pintype "passive"))
      (node (ref "C65") (pin "1") (pinfunction "1_1") (pintype "passive"))
      (node (ref "C67") (pin "1") (pinfunction "1_1") (pintype "passive"))
      (node (ref "C7") (pin "1") (pinfunction "1_1") (pintype "passive"))
      (node (ref "C70") (pin "1") (pinfunction "1_1") (pintype "passive"))
      (node (ref "C73") (pin "1") (pinfunction "1_1") (pintype "passive"))
      (node (ref "C77") (pin "1") (pinfunction "1_1") (pintype "passive"))
      (node (ref "C79") (pin "1") (pinfunction "1_1") (pintype "passive"))
      (node (ref "ERASE") (pin "P$2") (pinfunction "P$5_P$2") (pintype "bidirectional"))
      (node (ref "IC1") (pin "7") (pinfunction "V+_7") (pintype "power_in"))
      (node (ref "IC10") (pin "1") (pinfunction "VCC1_1") (pintype "input"))
      (node (ref "IC2") (pin "7") (pinfunction "V+_7") (pintype "power_in"))
      (node (ref "IC3") (pin "8") (pinfunction "VDD2_8") (pintype "bidirectional"))
      (node (ref "IC4") (pin "8") (pinfunction "VDD2_8") (pintype "bidirectional"))
      (node (ref "IC5") (pin "7") (pinfunction "V+_7") (pintype "power_in"))
      (node (ref "IC6") (pin "7") (pinfunction "V+_7") (pintype "power_in"))
      (node (ref "IC7") (pin "8") (pinfunction "VDD2_8") (pintype "bidirectional"))
      (node (ref "IC8") (pin "8") (pinfunction "VDD2_8") (pintype "bidirectional"))
      (node (ref "IC9") (pin "1") (pinfunction "VCC1_1") (pintype "input"))
      (node (ref "IWIFI") (pin "1") (pinfunction "1_1") (pintype "passive"))
      (node (ref "L1") (pin "1") (pinfunction "1_1") (pintype "passive"))
      (node (ref "L2") (pin "1") (pinfunction "1_1") (pintype "passive"))
      (node (ref "L3") (pin "1") (pinfunction "1_1") (pintype "passive"))
      (node (ref "R1") (pin "2") (pinfunction "2_2") (pintype "passive"))
      (node (ref "R42") (pin "2") (pinfunction "2_2") (pintype "passive"))
      (node (ref "R43") (pin "2") (pinfunction "2_2") (pintype "passive"))
      (node (ref "R48") (pin "2") (pinfunction "2_2") (pintype "passive"))
      (node (ref "R49") (pin "2") (pinfunction "2_2") (pintype "passive"))
      (node (ref "R54") (pin "1") (pinfunction "1_1") (pintype "passive"))
      (node (ref "R55") (pin "1") (pinfunction "1_1") (pintype "passive"))
      (node (ref "R58") (pin "2") (pinfunction "2_2") (pintype "passive"))
      (node (ref "U1") (pin "105") (pinfunction "VDDIO3_105") (pintype "power_in"))
      (node (ref "U1") (pin "11") (pinfunction "VDDIO1_11") (pintype "power_in"))
      (node (ref "U1") (pin "125") (pinfunction "VDDIO4_125") (pintype "power_in"))
      (node (ref "U1") (pin "52") (pinfunction "VDDBU_52") (pintype "power_in"))
      (node (ref "U1") (pin "57") (pinfunction "VDDIN_57") (pintype "power_in"))
      (node (ref "U1") (pin "62") (pinfunction "VDDIO2_62") (pintype "power_in"))
      (node (ref "U2") (pin "2") (pinfunction "OUT_2") (pintype "passive"))
      (node (ref "U3") (pin "1") (pinfunction "VDD1_1") (pintype "power_in"))
      (node (ref "U4") (pin "1") (pinfunction "VDD1_1") (pintype "power_in"))
      (node (ref "U5") (pin "1") (pinfunction "VDD1_1") (pintype "power_in"))
      (node (ref "U6") (pin "1") (pinfunction "VDD1_1") (pintype "power_in"))
      (node (ref "U7") (pin "PIN8") (pinfunction "VCC_PIN8") (pintype "bidirectional"))
      (node (ref "U8") (pin "+VOUT") (pinfunction "+VOUT_+VOUT") (pintype "bidirectional"))
      (node (ref "WIFI") (pin "A") (pinfunction "A_A") (pintype "passive"))
    )
    (net (code "2") (name "+5V") (class "Default")
      (node (ref "AMPSEAL1") (pin "24") (pinfunction "24_24") (pintype "passive"))
      (node (ref "AMPSEAL1") (pin "25") (pinfunction "25_25") (pintype "passive"))
      (node (ref "AMPSEAL1") (pin "26") (pinfunction "26_26") (pintype "passive"))
      (node (ref "AMPSEAL1") (pin "27") (pinfunction "27_27") (pintype "passive"))
      (node (ref "AMPSEAL1") (pin "28") (pinfunction "28_28") (pintype "passive"))
      (node (ref "C48") (pin "1") (pinfunction "1_1") (pintype "passive"))
      (node (ref "C50") (pin "1") (pinfunction "1_1") (pintype "passive"))
      (node (ref "C59") (pin "1") (pinfunction "1_1") (pintype "passive"))
      (node (ref "C64") (pin "1") (pinfunction "1_1") (pintype "passive"))
      (node (ref "C68") (pin "1") (pinfunction "1_1") (pintype "passive"))
      (node (ref "C71") (pin "1") (pinfunction "1_1") (pintype "passive"))
      (node (ref "IC10") (pin "9") (pinfunction "VCC2_9") (pintype "input"))
      (node (ref "IC3") (pin "1") (pinfunction "VDD1_1") (pintype "bidirectional"))
      (node (ref "IC4") (pin "1") (pinfunction "VDD1_1") (pintype "bidirectional"))
      (node (ref "IC7") (pin "1") (pinfunction "VDD1_1") (pintype "bidirectional"))
      (node (ref "IC8") (pin "1") (pinfunction "VDD1_1") (pintype "bidirectional"))
      (node (ref "IC9") (pin "9") (pinfunction "VCC2_9") (pintype "input"))
      (node (ref "R57") (pin "2") (pinfunction "2_2") (pintype "passive"))
      (node (ref "U9") (pin "P$3") (pinfunction "VO_P$3") (pintype "bidirectional"))
    )
    (net (code "3") (name "+12V") (class "Default")
      (node (ref "AMPSEAL1") (pin "2") (pinfunction "2_2") (pintype "passive"))
      (node (ref "C32") (pin "1") (pinfunction "1_1") (pintype "passive"))
      (node (ref "C33") (pin "1") (pinfunction "1_1") (pintype "passive"))
      (node (ref "C35") (pin "1") (pinfunction "1_1") (pintype "passive"))
      (node (ref "C36") (pin "1") (pinfunction "1_1") (pintype "passive"))
      (node (ref "C38") (pin "1") (pinfunction "1_1") (pintype "passive"))
      (node (ref "C39") (pin "1") (pinfunction "1_1") (pintype "passive"))
      (node (ref "C41") (pin "1") (pinfunction "1_1") (pintype "passive"))
      (node (ref "C42") (pin "1") (pinfunction "1_1") (pintype "passive"))
      (node (ref "C74") (pin "+") (pinfunction "+_+") (pintype "passive"))
      (node (ref "C75") (pin "1") (pinfunction "1_1") (pintype "passive"))
      (node (ref "C76") (pin "1") (pinfunction "1_1") (pintype "passive"))
      (node (ref "PTC") (pin "P$1") (pinfunction "1_P$1") (pintype "passive"))
      (node (ref "R56") (pin "2") (pinfunction "2_2") (pintype "passive"))
      (node (ref "U3") (pin "8") (pinfunction "VDD2_8") (pintype "power_in"))
      (node (ref "U4") (pin "8") (pinfunction "VDD2_8") (pintype "power_in"))
      (node (ref "U5") (pin "8") (pinfunction "VDD2_8") (pintype "power_in"))
      (node (ref "U6") (pin "8") (pinfunction "VDD2_8") (pintype "power_in"))
      (node (ref "U8") (pin "+VIN1") (pinfunction "+VIN1_+VIN1") (pintype "bidirectional"))
      (node (ref "U8") (pin "+VIN2") (pinfunction "+VIN2_+VIN2") (pintype "bidirectional"))
      (node (ref "U9") (pin "P$1") (pinfunction "VI_P$1") (pintype "bidirectional"))
    )
    (net (code "4") (name "/A0") (class "Default")
      (node (ref "C55") (pin "1") (pinfunction "1_1") (pintype "passive"))
      (node (ref "IC5") (pin "6") (pinfunction "OUT_6") (pintype "output"))
      (node (ref "R26") (pin "2") (pinfunction "2_2") (pintype "passive"))
      (node (ref "U1") (pin "78") (pinfunction "PA16_78") (pintype "bidirectional"))
    )
    (net (code "5") (name "/A1") (class "Default")
      (node (ref "C44") (pin "1") (pinfunction "1_1") (pintype "passive"))
      (node (ref "IC2") (pin "6") (pinfunction "OUT_6") (pintype "output"))
      (node (ref "R15") (pin "2") (pinfunction "2_2") (pintype "passive"))
      (node (ref "U1") (pin "79") (pinfunction "PA24_79") (pintype "bidirectional"))
    )
    (net (code "6") (name "/A2") (class "Default")
      (node (ref "C56") (pin "1") (pinfunction "1_1") (pintype "passive"))
      (node (ref "IC6") (pin "6") (pinfunction "OUT_6") (pintype "output"))
      (node (ref "R27") (pin "2") (pinfunction "2_2") (pintype "passive"))
      (node (ref "U1") (pin "80") (pinfunction "PA23_80") (pintype "bidirectional"))
    )
    (net (code "7") (name "/A3") (class "Default")
      (node (ref "C43") (pin "1") (pinfunction "1_1") (pintype "passive"))
      (node (ref "IC1") (pin "6") (pinfunction "OUT_6") (pintype "output"))
      (node (ref "R14") (pin "2") (pinfunction "2_2") (pintype "passive"))
      (node (ref "U1") (pin "81") (pinfunction "PA22_81") (pintype "bidirectional"))
    )
    (net (code "8") (name "/AIN0") (class "Default")
      (node (ref "AMPSEAL1") (pin "20") (pinfunction "20_20") (pintype "passive"))
      (node (ref "R16") (pin "2") (pinfunction "2_2") (pintype "passive"))
    )
    (net (code "9") (name "/AIN1") (class "Default")
      (node (ref "AMPSEAL1") (pin "21") (pinfunction "21_21") (pintype "passive"))
      (node (ref "R30") (pin "2") (pinfunction "2_2") (pintype "passive"))
    )
    (net (code "10") (name "/AIN2") (class "Default")
      (node (ref "AMPSEAL1") (pin "22") (pinfunction "22_22") (pintype "passive"))
      (node (ref "R18") (pin "2") (pinfunction "2_2") (pintype "passive"))
    )
    (net (code "11") (name "/AIN3") (class "Default")
      (node (ref "AMPSEAL1") (pin "23") (pinfunction "23_23") (pintype "passive"))
      (node (ref "R28") (pin "2") (pinfunction "2_2") (pintype "passive"))
    )
    (net (code "12") (name "/AVREF") (class "Default")
      (node (ref "C20") (pin "1") (pinfunction "1_1") (pintype "passive"))
      (node (ref "L3") (pin "2") (pinfunction "2_2") (pintype "passive"))
      (node (ref "U1") (pin "75") (pinfunction "ADVREF_75") (pintype "power_in"))
    )
    (net (code "13") (name "/CANH0") (class "Default")
      (node (ref "AMPSEAL1") (pin "9") (pinfunction "9_9") (pintype "passive"))
      (node (ref "IC9") (pin "12") (pinfunction "CANH_12") (pintype "input"))
      (node (ref "SJ1") (pin "1") (pinfunction "1_1") (pintype "passive"))
    )
    (net (code "14") (name "/CANH1") (class "Default")
      (node (ref "AMPSEAL1") (pin "11") (pinfunction "11_11") (pintype "passive"))
      (node (ref "IC10") (pin "12") (pinfunction "CANH_12") (pintype "input"))
      (node (ref "SJ3") (pin "1") (pinfunction "1_1") (pintype "passive"))
    )
    (net (code "15") (name "/CANL0") (class "Default")
      (node (ref "AMPSEAL1") (pin "10") (pinfunction "10_10") (pintype "passive"))
      (node (ref "IC9") (pin "13") (pinfunction "CANL_13") (pintype "input"))
      (node (ref "SJ2") (pin "1") (pinfunction "1_1") (pintype "passive"))
    )
    (net (code "16") (name "/CANL1") (class "Default")
      (node (ref "AMPSEAL1") (pin "12") (pinfunction "12_12") (pintype "passive"))
      (node (ref "IC10") (pin "13") (pinfunction "CANL_13") (pintype "input"))
      (node (ref "SJ4") (pin "1") (pinfunction "1_1") (pintype "passive"))
    )
    (net (code "17") (name "/CANRX0") (class "Default")
      (node (ref "IC9") (pin "3") (pinfunction "RXD_3") (pintype "input"))
      (node (ref "U1") (pin "24") (pinfunction "PA1_24") (pintype "bidirectional"))
    )
    (net (code "18") (name "/CANRX1") (class "Default")
      (node (ref "IC10") (pin "3") (pinfunction "RXD_3") (pintype "input"))
      (node (ref "U1") (pin "76") (pinfunction "PB15_76") (pintype "bidirectional"))
    )
    (net (code "19") (name "/CANTX0") (class "Default")
      (node (ref "IC9") (pin "6") (pinfunction "TXD_6") (pintype "input"))
      (node (ref "U1") (pin "23") (pinfunction "PA0_23") (pintype "bidirectional"))
    )
    (net (code "20") (name "/CANTX1") (class "Default")
      (node (ref "IC10") (pin "6") (pinfunction "TXD_6") (pintype "input"))
      (node (ref "U1") (pin "140") (pinfunction "PB14_140") (pintype "bidirectional"))
    )
    (net (code "21") (name "/D+") (class "Default")
      (node (ref "R3") (pin "1") (pinfunction "1_1") (pintype "passive"))
      (node (ref "U1") (pin "37") (pinfunction "DHSDP_37") (pintype "bidirectional"))
      (node (ref "X1") (pin "3") (pinfunction "3_3") (pintype "passive"))
      (node (ref "Z1") (pin "1") (pinfunction "1_1") (pintype "passive"))
    )
    (net (code "22") (name "/D-") (class "Default")
      (node (ref "R2") (pin "1") (pinfunction "1_1") (pintype "passive"))
      (node (ref "U1") (pin "38") (pinfunction "DHSDM_38") (pintype "bidirectional"))
      (node (ref "X1") (pin "2") (pinfunction "2_2") (pintype "passive"))
      (node (ref "Z2") (pin "1") (pinfunction "1_1") (pintype "passive"))
    )
    (net (code "23") (name "/D2") (class "Default")
      (node (ref "U1") (pin "144") (pinfunction "PB25_144") (pintype "bidirectional"))
      (node (ref "U4") (pin "3") (pinfunction "VIB_3") (pintype "input"))
    )
    (net (code "24") (name "/D3") (class "Default")
      (node (ref "U1") (pin "139") (pinfunction "PC28_139") (pintype "bidirectional"))
      (node (ref "U4") (pin "2") (pinfunction "VIA_2") (pintype "input"))
    )
    (net (code "25") (name "/D4") (class "Default")
      (node (ref "U1") (pin "137") (pinfunction "PC26_137") (pintype "bidirectional"))
      (node (ref "U6") (pin "3") (pinfunction "VIB_3") (pintype "input"))
    )
    (net (code "26") (name "/D5") (class "Default")
      (node (ref "U1") (pin "136") (pinfunction "PC25_136") (pintype "bidirectional"))
      (node (ref "U6") (pin "2") (pinfunction "VIA_2") (pintype "input"))
    )
    (net (code "27") (name "/D6") (class "Default")
      (node (ref "U1") (pin "135") (pinfunction "PC24_135") (pintype "bidirectional"))
      (node (ref "U5") (pin "3") (pinfunction "VIB_3") (pintype "input"))
    )
    (net (code "28") (name "/D7") (class "Default")
      (node (ref "U1") (pin "134") (pinfunction "PC23_134") (pintype "bidirectional"))
      (node (ref "U5") (pin "2") (pinfunction "VIA_2") (pintype "input"))
    )
    (net (code "29") (name "/D8") (class "Default")
      (node (ref "U1") (pin "133") (pinfunction "PC22_133") (pintype "bidirectional"))
      (node (ref "U3") (pin "3") (pinfunction "VIB_3") (pintype "input"))
    )
    (net (code "30") (name "/D9") (class "Default")
      (node (ref "U1") (pin "132") (pinfunction "PC21_132") (pintype "bidirectional"))
      (node (ref "U3") (pin "2") (pinfunction "VIA_2") (pintype "input"))
    )
    (net (code "31") (name "/D13") (class "Default")
      (node (ref "R5") (pin "2") (pinfunction "2_2") (pintype "passive"))
      (node (ref "U1") (pin "68") (pinfunction "PB27_68") (pintype "bidirectional"))
    )
    (net (code "32") (name "/D18") (class "Default")
      (node (ref "IWIFI") (pin "10") (pinfunction "10_10") (pintype "passive"))
      (node (ref "U1") (pin "4") (pinfunction "PA11_4") (pintype "bidirectional"))
    )
    (net (code "33") (name "/D42") (class "Default")
      (node (ref "IWIFI") (pin "11") (pinfunction "11_11") (pintype "passive"))
      (node (ref "U1") (pin "71") (pinfunction "PA19_71") (pintype "bidirectional"))
    )
    (net (code "34") (name "/D48") (class "Default")
      (node (ref "R42") (pin "1") (pinfunction "1_1") (pintype "passive"))
      (node (ref "R45") (pin "2") (pinfunction "2_2") (pintype "passive"))
      (node (ref "U1") (pin "97") (pinfunction "PC15_97") (pintype "bidirectional"))
    )
    (net (code "35") (name "/D49") (class "Default")
      (node (ref "R43") (pin "1") (pinfunction "1_1") (pintype "passive"))
      (node (ref "R47") (pin "2") (pinfunction "2_2") (pintype "passive"))
      (node (ref "U1") (pin "96") (pinfunction "PC14_96") (pintype "bidirectional"))
    )
    (net (code "36") (name "/D50") (class "Default")
      (node (ref "R48") (pin "1") (pinfunction "1_1") (pintype "passive"))
      (node (ref "R51") (pin "2") (pinfunction "2_2") (pintype "passive"))
      (node (ref "U1") (pin "95") (pinfunction "PC13_95") (pintype "bidirectional"))
    )
    (net (code "37") (name "/D51") (class "Default")
      (node (ref "R49") (pin "1") (pinfunction "1_1") (pintype "passive"))
      (node (ref "R53") (pin "2") (pinfunction "2_2") (pintype "passive"))
      (node (ref "U1") (pin "94") (pinfunction "PC12_94") (pintype "bidirectional"))
    )
    (net (code "38") (name "/DIN0") (class "Default")
      (node (ref "AMPSEAL1") (pin "32") (pinfunction "32_32") (pintype "passive"))
      (node (ref "R44") (pin "1") (pinfunction "1_1") (pintype "passive"))
    )
    (net (code "39") (name "/DIN1") (class "Default")
      (node (ref "AMPSEAL1") (pin "33") (pinfunction "33_33") (pintype "passive"))
      (node (ref "R46") (pin "1") (pinfunction "1_1") (pintype "passive"))
    )
    (net (code "40") (name "/DIN2") (class "Default")
      (node (ref "AMPSEAL1") (pin "34") (pinfunction "34_34") (pintype "passive"))
      (node (ref "R50") (pin "1") (pinfunction "1_1") (pintype "passive"))
    )
    (net (code "41") (name "/DIN3") (class "Default")
      (node (ref "AMPSEAL1") (pin "35") (pinfunction "35_35") (pintype "passive"))
      (node (ref "R52") (pin "1") (pinfunction "1_1") (pintype "passive"))
    )
    (net (code "42") (name "/DOUT0") (class "Default")
      (node (ref "AMPSEAL1") (pin "3") (pinfunction "3_3") (pintype "passive"))
      (node (ref "D1") (pin "C") (pinfunction "C_C") (pintype "passive"))
      (node (ref "T1") (pin "2") (pinfunction "D_2") (pintype "passive"))
      (node (ref "T1") (pin "4") (pinfunction "D_4") (pintype "passive"))
    )
    (net (code "43") (name "/DOUT1") (class "Default")
      (node (ref "AMPSEAL1") (pin "4") (pinfunction "4_4") (pintype "passive"))
      (node (ref "D2") (pin "C") (pinfunction "C_C") (pintype "passive"))
      (node (ref "T2") (pin "2") (pinfunction "D_2") (pintype "passive"))
      (node (ref "T2") (pin "4") (pinfunction "D_4") (pintype "passive"))
    )
    (net (code "44") (name "/DOUT2") (class "Default")
      (node (ref "AMPSEAL1") (pin "5") (pinfunction "5_5") (pintype "passive"))
      (node (ref "D3") (pin "C") (pinfunction "C_C") (pintype "passive"))
      (node (ref "T3") (pin "2") (pinfunction "D_2") (pintype "passive"))
      (node (ref "T3") (pin "4") (pinfunction "D_4") (pintype "passive"))
    )
    (net (code "45") (name "/DOUT3") (class "Default")
      (node (ref "AMPSEAL1") (pin "6") (pinfunction "6_6") (pintype "passive"))
      (node (ref "D4") (pin "C") (pinfunction "C_C") (pintype "passive"))
      (node (ref "T4") (pin "2") (pinfunction "D_2") (pintype "passive"))
      (node (ref "T4") (pin "4") (pinfunction "D_4") (pintype "passive"))
    )
    (net (code "46") (name "/DOUT4") (class "Default")
      (node (ref "AMPSEAL1") (pin "15") (pinfunction "15_15") (pintype "passive"))
      (node (ref "D5") (pin "C") (pinfunction "C_C") (pintype "passive"))
      (node (ref "T5") (pin "2") (pinfunction "D_2") (pintype "passive"))
      (node (ref "T5") (pin "4") (pinfunction "D_4") (pintype "passive"))
    )
    (net (code "47") (name "/DOUT5") (class "Default")
      (node (ref "AMPSEAL1") (pin "16") (pinfunction "16_16") (pintype "passive"))
      (node (ref "D6") (pin "C") (pinfunction "C_C") (pintype "passive"))
      (node (ref "T6") (pin "2") (pinfunction "D_2") (pintype "passive"))
      (node (ref "T6") (pin "4") (pinfunction "D_4") (pintype "passive"))
    )
    (net (code "48") (name "/DOUT6") (class "Default")
      (node (ref "AMPSEAL1") (pin "17") (pinfunction "17_17") (pintype "passive"))
      (node (ref "D7") (pin "C") (pinfunction "C_C") (pintype "passive"))
      (node (ref "T7") (pin "2") (pinfunction "D_2") (pintype "passive"))
      (node (ref "T7") (pin "4") (pinfunction "D_4") (pintype "passive"))
    )
    (net (code "49") (name "/DOUT7") (class "Default")
      (node (ref "AMPSEAL1") (pin "18") (pinfunction "18_18") (pintype "passive"))
      (node (ref "D8") (pin "C") (pinfunction "C_C") (pintype "passive"))
      (node (ref "T8") (pin "2") (pinfunction "D_2") (pintype "passive"))
      (node (ref "T8") (pin "4") (pinfunction "D_4") (pintype "passive"))
    )
    (net (code "50") (name "/MASTER-RESET") (class "Default")
      (node (ref "C28") (pin "2") (pinfunction "2_2") (pintype "passive"))
      (node (ref "RESET") (pin "P$2") (pinfunction "P$5_P$2") (pintype "bidirectional"))
      (node (ref "U1") (pin "47") (pinfunction "NRSTB_47") (pintype "input"))
    )
    (net (code "51") (name "/MDRIVE0") (class "Default")
      (node (ref "R12") (pin "1") (pinfunction "1_1") (pintype "passive"))
      (node (ref "T1") (pin "1") (pinfunction "G_1") (pintype "passive"))
      (node (ref "U6") (pin "6") (pinfunction "VOB_6") (pintype "output"))
    )
    (net (code "52") (name "/MDRIVE1") (class "Default")
      (node (ref "R13") (pin "1") (pinfunction "1_1") (pintype "passive"))
      (node (ref "T2") (pin "1") (pinfunction "G_1") (pintype "passive"))
      (node (ref "U6") (pin "7") (pinfunction "VOA_7") (pintype "output"))
    )
    (net (code "53") (name "/MDRIVE2") (class "Default")
      (node (ref "R10") (pin "1") (pinfunction "1_1") (pintype "passive"))
      (node (ref "T3") (pin "1") (pinfunction "G_1") (pintype "passive"))
      (node (ref "U5") (pin "6") (pinfunction "VOB_6") (pintype "output"))
    )
    (net (code "54") (name "/MDRIVE3") (class "Default")
      (node (ref "R11") (pin "1") (pinfunction "1_1") (pintype "passive"))
      (node (ref "T4") (pin "1") (pinfunction "G_1") (pintype "passive"))
      (node (ref "U5") (pin "7") (pinfunction "VOA_7") (pintype "output"))
    )
    (net (code "55") (name "/MDRIVE4") (class "Default")
      (node (ref "R8") (pin "1") (pinfunction "1_1") (pintype "passive"))
      (node (ref "T5") (pin "1") (pinfunction "G_1") (pintype "passive"))
      (node (ref "U4") (pin "6") (pinfunction "VOB_6") (pintype "output"))
    )
    (net (code "56") (name "/MDRIVE5") (class "Default")
      (node (ref "R9") (pin "1") (pinfunction "1_1") (pintype "passive"))
      (node (ref "T6") (pin "1") (pinfunction "G_1") (pintype "passive"))
      (node (ref "U4") (pin "7") (pinfunction "VOA_7") (pintype "output"))
    )
    (net (code "57") (name "/MDRIVE6") (class "Default")
      (node (ref "R6") (pin "1") (pinfunction "1_1") (pintype "passive"))
      (node (ref "T7") (pin "1") (pinfunction "G_1") (pintype "passive"))
      (node (ref "U3") (pin "6") (pinfunction "VOB_6") (pintype "output"))
    )
    (net (code "58") (name "/MDRIVE7") (class "Default")
      (node (ref "R7") (pin "1") (pinfunction "1_1") (pintype "passive"))
      (node (ref "T8") (pin "1") (pinfunction "G_1") (pintype "passive"))
      (node (ref "U3") (pin "7") (pinfunction "VOA_7") (pintype "output"))
    )
    (net (code "59") (name "/RX2") (class "Default")
      (node (ref "IWIFI") (pin "4") (pinfunction "4_4") (pintype "passive"))
      (node (ref "U1") (pin "5") (pinfunction "PA12_5") (pintype "bidirectional"))
    )
    (net (code "60") (name "/SCL") (class "Default")
      (node (ref "R54") (pin "2") (pinfunction "2_2") (pintype "passive"))
      (node (ref "U1") (pin "87") (pinfunction "PB13_87") (pintype "bidirectional"))
      (node (ref "U7") (pin "PIN6") (pinfunction "SCL_PIN6") (pintype "bidirectional"))
    )
    (net (code "61") (name "/SDA") (class "Default")
      (node (ref "R55") (pin "2") (pinfunction "2_2") (pintype "passive"))
      (node (ref "U1") (pin "86") (pinfunction "PB12_86") (pintype "bidirectional"))
      (node (ref "U7") (pin "PIN5") (pinfunction "SDA_PIN5") (pintype "bidirectional"))
    )
    (net (code "62") (name "/TX2") (class "Default")
      (node (ref "IWIFI") (pin "3") (pinfunction "3_3") (pintype "passive"))
      (node (ref "U1") (pin "6") (pinfunction "PA13_6") (pintype "bidirectional"))
    )
    (net (code "63") (name "/VBG") (class "Default")
      (node (ref "C27") (pin "1") (pinfunction "1_1") (pintype "passive"))
      (node (ref "R4") (pin "2") (pinfunction "2_2") (pintype "passive"))
      (node (ref "U1") (pin "40") (pinfunction "VBG_40") (pintype "passive"))
    )
    (net (code "64") (name "/VBUS") (class "Default")
      (node (ref "C29") (pin "1") (pinfunction "1_1") (pintype "passive"))
      (node (ref "U1") (pin "39") (pinfunction "VBUS_39") (pintype "power_in"))
      (node (ref "U2") (pin "3") (pinfunction "IN_3") (pintype "input"))
      (node (ref "X1") (pin "1") (pinfunction "1_1") (pintype "passive"))
    )
    (net (code "65") (name "/VDDANA") (class "Default")
      (node (ref "C10") (pin "1") (pinfunction "1_1") (pintype "passive"))
      (node (ref "C11") (pin "1") (pinfunction "1_1") (pintype "passive"))
      (node (ref "L1") (pin "2") (pinfunction "2_2") (pintype "passive"))
      (node (ref "U1") (pin "73") (pinfunction "VDDANA_73") (pintype "power_in"))
    )
    (net (code "66") (name "/VDDOUT") (class "Default")
      (node (ref "C12") (pin "1") (pinfunction "1_1") (pintype "passive"))
      (node (ref "C13") (pin "1") (pinfunction "1_1") (pintype "passive"))
      (node (ref "C14") (pin "1") (pinfunction "1_1") (pintype "passive"))
      (node (ref "C15") (pin "1") (pinfunction "1_1") (pintype "passive"))
      (node (ref "C16") (pin "1") (pinfunction "1_1") (pintype "passive"))
      (node (ref "C17") (pin "1") (pinfunction "1_1") (pintype "passive"))
      (node (ref "C18") (pin "1") (pinfunction "1_1") (pintype "passive"))
      (node (ref "L4") (pin "1") (pinfunction "1_1") (pintype "passive"))
      (node (ref "U1") (pin "10") (pinfunction "VDDCORE1_10") (pintype "input"))
      (node (ref "U1") (pin "104") (pinfunction "VDDCORE4_104") (pintype "input"))
      (node (ref "U1") (pin "124") (pinfunction "VDDCORE5_124") (pintype "input"))
      (node (ref "U1") (pin "45") (pinfunction "VDDCORE2_45") (pintype "input"))
      (node (ref "U1") (pin "56") (pinfunction "VDDOUT_56") (pintype "output"))
      (node (ref "U1") (pin "61") (pinfunction "VDDCORE3_61") (pintype "input"))
    )
    (net (code "67") (name "/VDDOUTMI") (class "Default")
      (node (ref "C8") (pin "1") (pinfunction "1_1") (pintype "passive"))
      (node (ref "C9") (pin "1") (pinfunction "1_1") (pintype "passive"))
      (node (ref "L2") (pin "2") (pinfunction "2_2") (pintype "passive"))
      (node (ref "U1") (pin "41") (pinfunction "VDDUTMI_41") (pintype "input"))
    )
    (net (code "68") (name "/VDDPLL") (class "Default")
      (node (ref "C21") (pin "1") (pinfunction "1_1") (pintype "passive"))
      (node (ref "C22") (pin "1") (pinfunction "1_1") (pintype "passive"))
      (node (ref "L4") (pin "2") (pinfunction "2_2") (pintype "passive"))
      (node (ref "U1") (pin "34") (pinfunction "VDDPLL_34") (pintype "input"))
    )
    (net (code "69") (name "/VIN(+12V)") (class "Default")
      (node (ref "AMPSEAL1") (pin "1") (pinfunction "1_1") (pintype "passive"))
      (node (ref "D9") (pin "A") (pinfunction "A_A") (pintype "passive"))
    )
    (net (code "70") (name "/XIN") (class "Default")
      (node (ref "C24") (pin "1") (pinfunction "1_1") (pintype "passive"))
      (node (ref "U1") (pin "36") (pinfunction "XIN_36") (pintype "input"))
      (node (ref "Y1") (pin "1") (pinfunction "C1_1") (pintype "passive"))
    )
    (net (code "71") (name "/XIN32") (class "Default")
      (node (ref "C26") (pin "1") (pinfunction "1_1") (pintype "passive"))
      (node (ref "U1") (pin "48") (pinfunction "XIN32_48") (pintype "output"))
      (node (ref "Y2") (pin "P$2") (pinfunction "2_P$2") (pintype "bidirectional"))
    )
    (net (code "72") (name "/XOUT") (class "Default")
      (node (ref "C23") (pin "1") (pinfunction "1_1") (pintype "passive"))
      (node (ref "U1") (pin "35") (pinfunction "XOUT_35") (pintype "output"))
      (node (ref "Y1") (pin "3") (pinfunction "C2_3") (pintype "passive"))
    )
    (net (code "73") (name "/XOUT32") (class "Default")
      (node (ref "C25") (pin "1") (pinfunction "1_1") (pintype "passive"))
      (node (ref "U1") (pin "49") (pinfunction "XOUT32_49") (pintype "output"))
      (node (ref "Y2") (pin "P$1") (pinfunction "1_P$1") (pintype "bidirectional"))
    )
    (net (code "74") (name "GND") (class "Default")
      (node (ref "+12V") (pin "C") (pinfunction "C_C") (pintype "passive"))
      (node (ref "+5V") (pin "C") (pinfunction "C_C") (pintype "passive"))
      (node (ref "AMPSEAL1") (pin "13") (pinfunction "13_13") (pintype "passive"))
      (node (ref "AMPSEAL1") (pin "14") (pinfunction "14_14") (pintype "passive"))
      (node (ref "AMPSEAL1") (pin "19") (pinfunction "19_19") (pintype "passive"))
      (node (ref "AMPSEAL1") (pin "29") (pinfunction "29_29") (pintype "passive"))
      (node (ref "AMPSEAL1") (pin "30") (pinfunction "30_30") (pintype "passive"))
      (node (ref "AMPSEAL1") (pin "31") (pinfunction "31_31") (pintype "passive"))
      (node (ref "AMPSEAL1") (pin "7") (pinfunction "7_7") (pintype "passive"))
      (node (ref "AMPSEAL1") (pin "8") (pinfunction "8_8") (pintype "passive"))
      (node (ref "C32") (pin "2") (pinfunction "2_2") (pintype "passive"))
      (node (ref "C33") (pin "2") (pinfunction "2_2") (pintype "passive"))
      (node (ref "C35") (pin "2") (pinfunction "2_2") (pintype "passive"))
      (node (ref "C36") (pin "2") (pinfunction "2_2") (pintype "passive"))
      (node (ref "C38") (pin "2") (pinfunction "2_2") (pintype "passive"))
      (node (ref "C39") (pin "2") (pinfunction "2_2") (pintype "passive"))
      (node (ref "C41") (pin "2") (pinfunction "2_2") (pintype "passive"))
      (node (ref "C42") (pin "2") (pinfunction "2_2") (pintype "passive"))
      (node (ref "C47") (pin "2") (pinfunction "2_2") (pintype "passive"))
      (node (ref "C48") (pin "2") (pinfunction "2_2") (pintype "passive"))
      (node (ref "C49") (pin "2") (pinfunction "2_2") (pintype "passive"))
      (node (ref "C50") (pin "2") (pinfunction "2_2") (pintype "passive"))
      (node (ref "C58") (pin "2") (pinfunction "2_2") (pintype "passive"))
      (node (ref "C59") (pin "2") (pinfunction "2_2") (pintype "passive"))
      (node (ref "C63") (pin "2") (pinfunction "2_2") (pintype "passive"))
      (node (ref "C64") (pin "2") (pinfunction "2_2") (pintype "passive"))
      (node (ref "C68") (pin "2") (pinfunction "2_2") (pintype "passive"))
      (node (ref "C69") (pin "2") (pinfunction "2_2") (pintype "passive"))
      (node (ref "C71") (pin "2") (pinfunction "2_2") (pintype "passive"))
      (node (ref "C72") (pin "2") (pinfunction "2_2") (pintype "passive"))
      (node (ref "C74") (pin "-") (pinfunction "-_-") (pintype "passive"))
      (node (ref "C75") (pin "2") (pinfunction "2_2") (pintype "passive"))
      (node (ref "C76") (pin "2") (pinfunction "2_2") (pintype "passive"))
      (node (ref "C78") (pin "1") (pinfunction "1_1") (pintype "passive"))
      (node (ref "D1") (pin "A") (pinfunction "A_A") (pintype "passive"))
      (node (ref "D2") (pin "A") (pinfunction "A_A") (pintype "passive"))
      (node (ref "D3") (pin "A") (pinfunction "A_A") (pintype "passive"))
      (node (ref "D4") (pin "A") (pinfunction "A_A") (pintype "passive"))
      (node (ref "D5") (pin "A") (pinfunction "A_A") (pintype "passive"))
      (node (ref "D6") (pin "A") (pinfunction "A_A") (pintype "passive"))
      (node (ref "D7") (pin "A") (pinfunction "A_A") (pintype "passive"))
      (node (ref "D8") (pin "A") (pinfunction "A_A") (pintype "passive"))
      (node (ref "IC10") (pin "10") (pinfunction "GND2_10") (pintype "input"))
      (node (ref "IC10") (pin "15") (pinfunction "GND2_15") (pintype "input"))
      (node (ref "IC10") (pin "16") (pinfunction "GND2_16") (pintype "input"))
      (node (ref "IC3") (pin "3") (pinfunction "SHDN_3") (pintype "bidirectional"))
      (node (ref "IC3") (pin "4") (pinfunction "GND1_4") (pintype "bidirectional"))
      (node (ref "IC4") (pin "3") (pinfunction "SHDN_3") (pintype "bidirectional"))
      (node (ref "IC4") (pin "4") (pinfunction "GND1_4") (pintype "bidirectional"))
      (node (ref "IC7") (pin "3") (pinfunction "SHDN_3") (pintype "bidirectional"))
      (node (ref "IC7") (pin "4") (pinfunction "GND1_4") (pintype "bidirectional"))
      (node (ref "IC8") (pin "3") (pinfunction "SHDN_3") (pintype "bidirectional"))
      (node (ref "IC8") (pin "4") (pinfunction "GND1_4") (pintype "bidirectional"))
      (node (ref "IC9") (pin "10") (pinfunction "GND2_10") (pintype "input"))
      (node (ref "IC9") (pin "15") (pinfunction "GND2_15") (pintype "input"))
      (node (ref "IC9") (pin "16") (pinfunction "GND2_16") (pintype "input"))
      (node (ref "OK1") (pin "2") (pinfunction "C_2") (pintype "passive"))
      (node (ref "OK1") (pin "4") (pinfunction "C_4") (pintype "passive"))
      (node (ref "OK2") (pin "2") (pinfunction "C_2") (pintype "passive"))
      (node (ref "OK2") (pin "4") (pinfunction "C_4") (pintype "passive"))
      (node (ref "R10") (pin "2") (pinfunction "2_2") (pintype "passive"))
      (node (ref "R11") (pin "2") (pinfunction "2_2") (pintype "passive"))
      (node (ref "R12") (pin "2") (pinfunction "2_2") (pintype "passive"))
      (node (ref "R13") (pin "2") (pinfunction "2_2") (pintype "passive"))
      (node (ref "R20") (pin "1") (pinfunction "1_1") (pintype "passive"))
      (node (ref "R22") (pin "1") (pinfunction "1_1") (pintype "passive"))
      (node (ref "R32") (pin "1") (pinfunction "1_1") (pintype "passive"))
      (node (ref "R34") (pin "1") (pinfunction "1_1") (pintype "passive"))
      (node (ref "R6") (pin "2") (pinfunction "2_2") (pintype "passive"))
      (node (ref "R7") (pin "2") (pinfunction "2_2") (pintype "passive"))
      (node (ref "R8") (pin "2") (pinfunction "2_2") (pintype "passive"))
      (node (ref "R9") (pin "2") (pinfunction "2_2") (pintype "passive"))
      (node (ref "T1") (pin "3") (pinfunction "S_3") (pintype "passive"))
      (node (ref "T2") (pin "3") (pinfunction "S_3") (pintype "passive"))
      (node (ref "T3") (pin "3") (pinfunction "S_3") (pintype "passive"))
      (node (ref "T4") (pin "3") (pinfunction "S_3") (pintype "passive"))
      (node (ref "T5") (pin "3") (pinfunction "S_3") (pintype "passive"))
      (node (ref "T6") (pin "3") (pinfunction "S_3") (pintype "passive"))
      (node (ref "T7") (pin "3") (pinfunction "S_3") (pintype "passive"))
      (node (ref "T8") (pin "3") (pinfunction "S_3") (pintype "passive"))
      (node (ref "TVS") (pin "A") (pinfunction "A_A") (pintype "passive"))
      (node (ref "U3") (pin "5") (pinfunction "GND2_5") (pintype "passive"))
      (node (ref "U4") (pin "5") (pinfunction "GND2_5") (pintype "passive"))
      (node (ref "U5") (pin "5") (pinfunction "GND2_5") (pintype "passive"))
      (node (ref "U6") (pin "5") (pinfunction "GND2_5") (pintype "passive"))
      (node (ref "U8") (pin "-VIN1") (pinfunction "-VIN1_-VIN1") (pintype "bidirectional"))
      (node (ref "U8") (pin "-VIN2") (pinfunction "-VIN2_-VIN2") (pintype "bidirectional"))
      (node (ref "U9") (pin "P$2") (pinfunction "GND_P$2") (pintype "bidirectional"))
      (node (ref "ZEN") (pin "A") (pinfunction "A_A") (pintype "passive"))
    )
    (net (code "75") (name "IGND") (class "Default")
      (node (ref "+3.3V") (pin "C") (pinfunction "C_C") (pintype "passive"))
      (node (ref "C1") (pin "2") (pinfunction "2_2") (pintype "passive"))
      (node (ref "C10") (pin "2") (pinfunction "2_2") (pintype "passive"))
      (node (ref "C11") (pin "2") (pinfunction "2_2") (pintype "passive"))
      (node (ref "C12") (pin "2") (pinfunction "2_2") (pintype "passive"))
      (node (ref "C13") (pin "2") (pinfunction "2_2") (pintype "passive"))
      (node (ref "C14") (pin "2") (pinfunction "2_2") (pintype "passive"))
      (node (ref "C15") (pin "2") (pinfunction "2_2") (pintype "passive"))
      (node (ref "C16") (pin "2") (pinfunction "2_2") (pintype "passive"))
      (node (ref "C17") (pin "2") (pinfunction "2_2") (pintype "passive"))
      (node (ref "C18") (pin "2") (pinfunction "2_2") (pintype "passive"))
      (node (ref "C19") (pin "2") (pinfunction "2_2") (pintype "passive"))
      (node (ref "C2") (pin "2") (pinfunction "2_2") (pintype "passive"))
      (node (ref "C20") (pin "2") (pinfunction "2_2") (pintype "passive"))
      (node (ref "C21") (pin "2") (pinfunction "2_2") (pintype "passive"))
      (node (ref "C22") (pin "2") (pinfunction "2_2") (pintype "passive"))
      (node (ref "C23") (pin "2") (pinfunction "2_2") (pintype "passive"))
      (node (ref "C24") (pin "2") (pinfunction "2_2") (pintype "passive"))
      (node (ref "C25") (pin "2") (pinfunction "2_2") (pintype "passive"))
      (node (ref "C26") (pin "2") (pinfunction "2_2") (pintype "passive"))
      (node (ref "C27") (pin "2") (pinfunction "2_2") (pintype "passive"))
      (node (ref "C29") (pin "2") (pinfunction "2_2") (pintype "passive"))
      (node (ref "C3") (pin "2") (pinfunction "2_2") (pintype "passive"))
      (node (ref "C30") (pin "2") (pinfunction "2_2") (pintype "passive"))
      (node (ref "C31") (pin "2") (pinfunction "2_2") (pintype "passive"))
      (node (ref "C34") (pin "2") (pinfunction "2_2") (pintype "passive"))
      (node (ref "C37") (pin "2") (pinfunction "2_2") (pintype "passive"))
      (node (ref "C4") (pin "2") (pinfunction "2_2") (pintype "passive"))
      (node (ref "C40") (pin "2") (pinfunction "2_2") (pintype "passive"))
      (node (ref "C45") (pin "2") (pinfunction "2_2") (pintype "passive"))
      (node (ref "C46") (pin "2") (pinfunction "2_2") (pintype "passive"))
      (node (ref "C5") (pin "2") (pinfunction "2_2") (pintype "passive"))
      (node (ref "C51") (pin "2") (pinfunction "2_2") (pintype "passive"))
      (node (ref "C52") (pin "2") (pinfunction "2_2") (pintype "passive"))
      (node (ref "C53") (pin "2") (pinfunction "2_2") (pintype "passive"))
      (node (ref "C54") (pin "2") (pinfunction "2_2") (pintype "passive"))
      (node (ref "C57") (pin "2") (pinfunction "2_2") (pintype "passive"))
      (node (ref "C6") (pin "2") (pinfunction "2_2") (pintype "passive"))
      (node (ref "C60") (pin "2") (pinfunction "2_2") (pintype "passive"))
      (node (ref "C61") (pin "2") (pinfunction "2_2") (pintype "passive"))
      (node (ref "C62") (pin "2") (pinfunction "2_2") (pintype "passive"))
      (node (ref "C65") (pin "2") (pinfunction "2_2") (pintype "passive"))
      (node (ref "C66") (pin "2") (pinfunction "2_2") (pintype "passive"))
      (node (ref "C67") (pin "2") (pinfunction "2_2") (pintype "passive"))
      (node (ref "C7") (pin "2") (pinfunction "2_2") (pintype "passive"))
      (node (ref "C70") (pin "2") (pinfunction "2_2") (pintype "passive"))
      (node (ref "C73") (pin "2") (pinfunction "2_2") (pintype "passive"))
      (node (ref "C77") (pin "2") (pinfunction "2_2") (pintype "passive"))
      (node (ref "C78") (pin "2") (pinfunction "2_2") (pintype "passive"))
      (node (ref "C79") (pin "2") (pinfunction "2_2") (pintype "passive"))
      (node (ref "C8") (pin "2") (pinfunction "2_2") (pintype "passive"))
      (node (ref "C9") (pin "2") (pinfunction "2_2") (pintype "passive"))
      (node (ref "IC1") (pin "4") (pinfunction "V-_4") (pintype "power_in"))
      (node (ref "IC10") (pin "2") (pinfunction "GND1_2") (pintype "input"))
      (node (ref "IC10") (pin "7") (pinfunction "GND1_7") (pintype "input"))
      (node (ref "IC10") (pin "8") (pinfunction "GND1_8") (pintype "input"))
      (node (ref "IC2") (pin "4") (pinfunction "V-_4") (pintype "power_in"))
      (node (ref "IC3") (pin "5") (pinfunction "GND2_5") (pintype "bidirectional"))
      (node (ref "IC4") (pin "5") (pinfunction "GND2_5") (pintype "bidirectional"))
      (node (ref "IC5") (pin "4") (pinfunction "V-_4") (pintype "power_in"))
      (node (ref "IC6") (pin "4") (pinfunction "V-_4") (pintype "power_in"))
      (node (ref "IC7") (pin "5") (pinfunction "GND2_5") (pintype "bidirectional"))
      (node (ref "IC8") (pin "5") (pinfunction "GND2_5") (pintype "bidirectional"))
      (node (ref "IC9") (pin "2") (pinfunction "GND1_2") (pintype "input"))
      (node (ref "IC9") (pin "7") (pinfunction "GND1_7") (pintype "input"))
      (node (ref "IC9") (pin "8") (pinfunction "GND1_8") (pintype "input"))
      (node (ref "IWIFI") (pin "2") (pinfunction "2_2") (pintype "passive"))
      (node (ref "LED") (pin "C") (pinfunction "C_C") (pintype "passive"))
      (node (ref "OK1") (pin "5") (pinfunction "EMIT_5") (pintype "passive"))
      (node (ref "OK1") (pin "7") (pinfunction "EMIT_7") (pintype "passive"))
      (node (ref "OK2") (pin "5") (pinfunction "EMIT_5") (pintype "passive"))
      (node (ref "OK2") (pin "7") (pinfunction "EMIT_7") (pintype "passive"))
      (node (ref "R24") (pin "2") (pinfunction "2_2") (pintype "passive"))
      (node (ref "R25") (pin "2") (pinfunction "2_2") (pintype "passive"))
      (node (ref "R36") (pin "2") (pinfunction "2_2") (pintype "passive"))
      (node (ref "R37") (pin "2") (pinfunction "2_2") (pintype "passive"))
      (node (ref "R4") (pin "1") (pinfunction "1_1") (pintype "passive"))
      (node (ref "RESET") (pin "P$1") (pinfunction "P$4_P$1") (pintype "bidirectional"))
      (node (ref "U1") (pin "106") (pinfunction "GND3_106") (pintype "power_in"))
      (node (ref "U1") (pin "12") (pinfunction "GND1_12") (pintype "power_in"))
      (node (ref "U1") (pin "126") (pinfunction "GND4_126") (pintype "power_in"))
      (node (ref "U1") (pin "33") (pinfunction "GNDPLL_33") (pintype "power_in"))
      (node (ref "U1") (pin "44") (pinfunction "GNDUTMI_44") (pintype "power_in"))
      (node (ref "U1") (pin "46") (pinfunction "JTAGSEL_46") (pintype "input"))
      (node (ref "U1") (pin "54") (pinfunction "GNDBU_54") (pintype "power_in"))
      (node (ref "U1") (pin "58") (pinfunction "GND2_58") (pintype "power_in"))
      (node (ref "U1") (pin "74") (pinfunction "GNDANA_74") (pintype "power_in"))
      (node (ref "U2") (pin "1") (pinfunction "ADJ_1") (pintype "input"))
      (node (ref "U3") (pin "4") (pinfunction "GND1_4") (pintype "passive"))
      (node (ref "U4") (pin "4") (pinfunction "GND1_4") (pintype "passive"))
      (node (ref "U5") (pin "4") (pinfunction "GND1_4") (pintype "passive"))
      (node (ref "U6") (pin "4") (pinfunction "GND1_4") (pintype "passive"))
      (node (ref "U7") (pin "PIN1") (pinfunction "NA1_PIN1") (pintype "bidirectional"))
      (node (ref "U7") (pin "PIN2") (pinfunction "NA2_PIN2") (pintype "bidirectional"))
      (node (ref "U7") (pin "PIN3") (pinfunction "E2_PIN3") (pintype "bidirectional"))
      (node (ref "U7") (pin "PIN4") (pinfunction "VSS_PIN4") (pintype "bidirectional"))
      (node (ref "U8") (pin "-VOUT") (pinfunction "-VOUT_-VOUT") (pintype "bidirectional"))
      (node (ref "X1") (pin "4") (pinfunction "4_4") (pintype "passive"))
      (node (ref "Y1") (pin "2") (pinfunction "GND_2") (pintype "passive"))
      (node (ref "Y1") (pin "4") (pinfunction "GND_4") (pintype "passive"))
      (node (ref "Z1") (pin "2") (pinfunction "2_2") (pintype "passive"))
      (node (ref "Z2") (pin "2") (pinfunction "2_2") (pintype "passive"))
    )
    (net (code "76") (name "Net-(+3.3V-PadA)") (class "Default")
      (node (ref "+3.3V") (pin "A") (pinfunction "A_A") (pintype "passive"))
      (node (ref "R58") (pin "1") (pinfunction "1_1") (pintype "passive"))
    )
    (net (code "77") (name "Net-(+5V-PadA)") (class "Default")
      (node (ref "+5V") (pin "A") (pinfunction "A_A") (pintype "passive"))
      (node (ref "R57") (pin "1") (pinfunction "1_1") (pintype "passive"))
    )
    (net (code "78") (name "Net-(+12V-PadA)") (class "Default")
      (node (ref "+12V") (pin "A") (pinfunction "A_A") (pintype "passive"))
      (node (ref "R56") (pin "1") (pinfunction "1_1") (pintype "passive"))
    )
    (net (code "79") (name "Net-(C69-Pad1)") (class "Default")
      (node (ref "C69") (pin "1") (pinfunction "1_1") (pintype "passive"))
      (node (ref "R38") (pin "1") (pinfunction "1_1") (pintype "passive"))
      (node (ref "R39") (pin "1") (pinfunction "1_1") (pintype "passive"))
    )
    (net (code "80") (name "Net-(C72-Pad1)") (class "Default")
      (node (ref "C72") (pin "1") (pinfunction "1_1") (pintype "passive"))
      (node (ref "R40") (pin "1") (pinfunction "1_1") (pintype "passive"))
      (node (ref "R41") (pin "1") (pinfunction "1_1") (pintype "passive"))
    )
    (net (code "81") (name "Net-(ERASE-P$4)") (class "Default")
      (node (ref "ERASE") (pin "P$1") (pinfunction "P$4_P$1") (pintype "bidirectional"))
      (node (ref "U1") (pin "130") (pinfunction "PC0_130") (pintype "bidirectional"))
    )
    (net (code "82") (name "Net-(IC1-+IN)") (class "Default")
      (node (ref "C53") (pin "1") (pinfunction "1_1") (pintype "passive"))
      (node (ref "IC1") (pin "3") (pinfunction "+IN_3") (pintype "input"))
      (node (ref "R21") (pin "2") (pinfunction "2_2") (pintype "passive"))
      (node (ref "R24") (pin "1") (pinfunction "1_1") (pintype "passive"))
    )
    (net (code "83") (name "Net-(IC1--IN)") (class "Default")
      (node (ref "C43") (pin "2") (pinfunction "2_2") (pintype "passive"))
      (node (ref "IC1") (pin "2") (pinfunction "-IN_2") (pintype "input"))
      (node (ref "R14") (pin "1") (pinfunction "1_1") (pintype "passive"))
      (node (ref "R17") (pin "2") (pinfunction "2_2") (pintype "passive"))
    )
    (net (code "84") (name "Net-(IC2-+IN)") (class "Default")
      (node (ref "C54") (pin "1") (pinfunction "1_1") (pintype "passive"))
      (node (ref "IC2") (pin "3") (pinfunction "+IN_3") (pintype "input"))
      (node (ref "R23") (pin "2") (pinfunction "2_2") (pintype "passive"))
      (node (ref "R25") (pin "1") (pinfunction "1_1") (pintype "passive"))
    )
    (net (code "85") (name "Net-(IC2--IN)") (class "Default")
      (node (ref "C44") (pin "2") (pinfunction "2_2") (pintype "passive"))
      (node (ref "IC2") (pin "2") (pinfunction "-IN_2") (pintype "input"))
      (node (ref "R15") (pin "1") (pinfunction "1_1") (pintype "passive"))
      (node (ref "R19") (pin "2") (pinfunction "2_2") (pintype "passive"))
    )
    (net (code "86") (name "Net-(IC3-VIN)") (class "Default")
      (node (ref "C47") (pin "1") (pinfunction "1_1") (pintype "passive"))
      (node (ref "IC3") (pin "2") (pinfunction "VIN_2") (pintype "bidirectional"))
      (node (ref "R16") (pin "1") (pinfunction "1_1") (pintype "passive"))
      (node (ref "R20") (pin "2") (pinfunction "2_2") (pintype "passive"))
    )
    (net (code "87") (name "Net-(IC3-VOUT+)") (class "Default")
      (node (ref "IC3") (pin "7") (pinfunction "VOUT+_7") (pintype "bidirectional"))
      (node (ref "R21") (pin "1") (pinfunction "1_1") (pintype "passive"))
    )
    (net (code "88") (name "Net-(IC3-VOUT-)") (class "Default")
      (node (ref "IC3") (pin "6") (pinfunction "VOUT-_6") (pintype "bidirectional"))
      (node (ref "R17") (pin "1") (pinfunction "1_1") (pintype "passive"))
    )
    (net (code "89") (name "Net-(IC4-VIN)") (class "Default")
      (node (ref "C49") (pin "1") (pinfunction "1_1") (pintype "passive"))
      (node (ref "IC4") (pin "2") (pinfunction "VIN_2") (pintype "bidirectional"))
      (node (ref "R18") (pin "1") (pinfunction "1_1") (pintype "passive"))
      (node (ref "R22") (pin "2") (pinfunction "2_2") (pintype "passive"))
    )
    (net (code "90") (name "Net-(IC4-VOUT+)") (class "Default")
      (node (ref "IC4") (pin "7") (pinfunction "VOUT+_7") (pintype "bidirectional"))
      (node (ref "R23") (pin "1") (pinfunction "1_1") (pintype "passive"))
    )
    (net (code "91") (name "Net-(IC4-VOUT-)") (class "Default")
      (node (ref "IC4") (pin "6") (pinfunction "VOUT-_6") (pintype "bidirectional"))
      (node (ref "R19") (pin "1") (pinfunction "1_1") (pintype "passive"))
    )
    (net (code "92") (name "Net-(IC5-+IN)") (class "Default")
      (node (ref "C62") (pin "1") (pinfunction "1_1") (pintype "passive"))
      (node (ref "IC5") (pin "3") (pinfunction "+IN_3") (pintype "input"))
      (node (ref "R33") (pin "2") (pinfunction "2_2") (pintype "passive"))
      (node (ref "R36") (pin "1") (pinfunction "1_1") (pintype "passive"))
    )
    (net (code "93") (name "Net-(IC5--IN)") (class "Default")
      (node (ref "C55") (pin "2") (pinfunction "2_2") (pintype "passive"))
      (node (ref "IC5") (pin "2") (pinfunction "-IN_2") (pintype "input"))
      (node (ref "R26") (pin "1") (pinfunction "1_1") (pintype "passive"))
      (node (ref "R29") (pin "2") (pinfunction "2_2") (pintype "passive"))
    )
    (net (code "94") (name "Net-(IC6-+IN)") (class "Default")
      (node (ref "C66") (pin "1") (pinfunction "1_1") (pintype "passive"))
      (node (ref "IC6") (pin "3") (pinfunction "+IN_3") (pintype "input"))
      (node (ref "R35") (pin "2") (pinfunction "2_2") (pintype "passive"))
      (node (ref "R37") (pin "1") (pinfunction "1_1") (pintype "passive"))
    )
    (net (code "95") (name "Net-(IC6--IN)") (class "Default")
      (node (ref "C56") (pin "2") (pinfunction "2_2") (pintype "passive"))
      (node (ref "IC6") (pin "2") (pinfunction "-IN_2") (pintype "input"))
      (node (ref "R27") (pin "1") (pinfunction "1_1") (pintype "passive"))
      (node (ref "R31") (pin "2") (pinfunction "2_2") (pintype "passive"))
    )
    (net (code "96") (name "Net-(IC7-VIN)") (class "Default")
      (node (ref "C58") (pin "1") (pinfunction "1_1") (pintype "passive"))
      (node (ref "IC7") (pin "2") (pinfunction "VIN_2") (pintype "bidirectional"))
      (node (ref "R28") (pin "1") (pinfunction "1_1") (pintype "passive"))
      (node (ref "R32") (pin "2") (pinfunction "2_2") (pintype "passive"))
    )
    (net (code "97") (name "Net-(IC7-VOUT+)") (class "Default")
      (node (ref "IC7") (pin "7") (pinfunction "VOUT+_7") (pintype "bidirectional"))
      (node (ref "R33") (pin "1") (pinfunction "1_1") (pintype "passive"))
    )
    (net (code "98") (name "Net-(IC7-VOUT-)") (class "Default")
      (node (ref "IC7") (pin "6") (pinfunction "VOUT-_6") (pintype "bidirectional"))
      (node (ref "R29") (pin "1") (pinfunction "1_1") (pintype "passive"))
    )
    (net (code "99") (name "Net-(IC8-VIN)") (class "Default")
      (node (ref "C63") (pin "1") (pinfunction "1_1") (pintype "passive"))
      (node (ref "IC8") (pin "2") (pinfunction "VIN_2") (pintype "bidirectional"))
      (node (ref "R30") (pin "1") (pinfunction "1_1") (pintype "passive"))
      (node (ref "R34") (pin "2") (pinfunction "2_2") (pintype "passive"))
    )
    (net (code "100") (name "Net-(IC8-VOUT+)") (class "Default")
      (node (ref "IC8") (pin "7") (pinfunction "VOUT+_7") (pintype "bidirectional"))
      (node (ref "R35") (pin "1") (pinfunction "1_1") (pintype "passive"))
    )
    (net (code "101") (name "Net-(IC8-VOUT-)") (class "Default")
      (node (ref "IC8") (pin "6") (pinfunction "VOUT-_6") (pintype "bidirectional"))
      (node (ref "R31") (pin "1") (pinfunction "1_1") (pintype "passive"))
    )
    (net (code "102") (name "Net-(IWIFI-Pad5)") (class "Default")
      (node (ref "IWIFI") (pin "5") (pinfunction "5_5") (pintype "passive"))
      (node (ref "IWIFI") (pin "7") (pinfunction "7_7") (pintype "passive"))
    )
    (net (code "103") (name "Net-(IWIFI-Pad12)") (class "Default")
      (node (ref "IWIFI") (pin "12") (pinfunction "12_12") (pintype "passive"))
      (node (ref "WIFI") (pin "C") (pinfunction "C_C") (pintype "passive"))
    )
    (net (code "104") (name "Net-(LED-PadA)") (class "Default")
      (node (ref "LED") (pin "A") (pinfunction "A_A") (pintype "passive"))
      (node (ref "R5") (pin "1") (pinfunction "1_1") (pintype "passive"))
    )
    (net (code "105") (name "Net-(OK1A-A)") (class "Default")
      (node (ref "OK1") (pin "1") (pinfunction "A_1") (pintype "passive"))
      (node (ref "R44") (pin "2") (pinfunction "2_2") (pintype "passive"))
    )
    (net (code "106") (name "Net-(OK1A-COL)") (class "Default")
      (node (ref "OK1") (pin "8") (pinfunction "COL_8") (pintype "passive"))
      (node (ref "R45") (pin "1") (pinfunction "1_1") (pintype "passive"))
    )
    (net (code "107") (name "Net-(OK1B-A)") (class "Default")
      (node (ref "OK1") (pin "3") (pinfunction "A_3") (pintype "passive"))
      (node (ref "R46") (pin "2") (pinfunction "2_2") (pintype "passive"))
    )
    (net (code "108") (name "Net-(OK1B-COL)") (class "Default")
      (node (ref "OK1") (pin "6") (pinfunction "COL_6") (pintype "passive"))
      (node (ref "R47") (pin "1") (pinfunction "1_1") (pintype "passive"))
    )
    (net (code "109") (name "Net-(OK2A-A)") (class "Default")
      (node (ref "OK2") (pin "1") (pinfunction "A_1") (pintype "passive"))
      (node (ref "R50") (pin "2") (pinfunction "2_2") (pintype "passive"))
    )
    (net (code "110") (name "Net-(OK2A-COL)") (class "Default")
      (node (ref "OK2") (pin "8") (pinfunction "COL_8") (pintype "passive"))
      (node (ref "R51") (pin "1") (pinfunction "1_1") (pintype "passive"))
    )
    (net (code "111") (name "Net-(OK2B-A)") (class "Default")
      (node (ref "OK2") (pin "3") (pinfunction "A_3") (pintype "passive"))
      (node (ref "R52") (pin "2") (pinfunction "2_2") (pintype "passive"))
    )
    (net (code "112") (name "Net-(OK2B-COL)") (class "Default")
      (node (ref "OK2") (pin "6") (pinfunction "COL_6") (pintype "passive"))
      (node (ref "R53") (pin "1") (pinfunction "1_1") (pintype "passive"))
    )
    (net (code "113") (name "Net-(PTC-2)") (class "Default")
      (node (ref "D9") (pin "C") (pinfunction "C_C") (pintype "passive"))
      (node (ref "PTC") (pin "P$2") (pinfunction "2_P$2") (pintype "passive"))
      (node (ref "TVS") (pin "C") (pinfunction "C_C") (pintype "passive"))
      (node (ref "ZEN") (pin "C") (pinfunction "C_C") (pintype "passive"))
    )
    (net (code "114") (name "Net-(R38-Pad2)") (class "Default")
      (node (ref "R38") (pin "2") (pinfunction "2_2") (pintype "passive"))
      (node (ref "SJ1") (pin "2") (pinfunction "2_2") (pintype "passive"))
    )
    (net (code "115") (name "Net-(R39-Pad2)") (class "Default")
      (node (ref "R39") (pin "2") (pinfunction "2_2") (pintype "passive"))
      (node (ref "SJ2") (pin "2") (pinfunction "2_2") (pintype "passive"))
    )
    (net (code "116") (name "Net-(R40-Pad2)") (class "Default")
      (node (ref "R40") (pin "2") (pinfunction "2_2") (pintype "passive"))
      (node (ref "SJ3") (pin "2") (pinfunction "2_2") (pintype "passive"))
    )
    (net (code "117") (name "Net-(R41-Pad2)") (class "Default")
      (node (ref "R41") (pin "2") (pinfunction "2_2") (pintype "passive"))
      (node (ref "SJ4") (pin "2") (pinfunction "2_2") (pintype "passive"))
    )
    (net (code "118") (name "Net-(U1-DFSDM)") (class "Default")
      (node (ref "R2") (pin "2") (pinfunction "2_2") (pintype "passive"))
      (node (ref "U1") (pin "43") (pinfunction "DFSDM_43") (pintype "input"))
    )
    (net (code "119") (name "Net-(U1-DFSDP)") (class "Default")
      (node (ref "R3") (pin "2") (pinfunction "2_2") (pintype "passive"))
      (node (ref "U1") (pin "42") (pinfunction "DFSDP_42") (pintype "input"))
    )
    (net (code "120") (name "Net-(U1-FWUP)") (class "Default")
      (node (ref "R1") (pin "1") (pinfunction "1_1") (pintype "passive"))
      (node (ref "U1") (pin "53") (pinfunction "FWUP_53") (pintype "input"))
    )
    (net (code "121") (name "unconnected-(IC1-NC-Pad8)") (class "Default")
      (node (ref "IC1") (pin "8") (pinfunction "NC_8") (pintype "no_connect"))
    )
    (net (code "122") (name "unconnected-(IC1-REF-Pad1)") (class "Default")
      (node (ref "IC1") (pin "1") (pinfunction "REF_1") (pintype "passive"))
    )
    (net (code "123") (name "unconnected-(IC1-SENSE-Pad5)") (class "Default")
      (node (ref "IC1") (pin "5") (pinfunction "SENSE_5") (pintype "passive"))
    )
    (net (code "124") (name "unconnected-(IC2-NC-Pad8)") (class "Default")
      (node (ref "IC2") (pin "8") (pinfunction "NC_8") (pintype "no_connect"))
    )
    (net (code "125") (name "unconnected-(IC2-REF-Pad1)") (class "Default")
      (node (ref "IC2") (pin "1") (pinfunction "REF_1") (pintype "passive"))
    )
    (net (code "126") (name "unconnected-(IC2-SENSE-Pad5)") (class "Default")
      (node (ref "IC2") (pin "5") (pinfunction "SENSE_5") (pintype "passive"))
    )
    (net (code "127") (name "unconnected-(IC5-NC-Pad8)") (class "Default")
      (node (ref "IC5") (pin "8") (pinfunction "NC_8") (pintype "no_connect"))
    )
    (net (code "128") (name "unconnected-(IC5-REF-Pad1)") (class "Default")
      (node (ref "IC5") (pin "1") (pinfunction "REF_1") (pintype "passive"))
    )
    (net (code "129") (name "unconnected-(IC5-SENSE-Pad5)") (class "Default")
      (node (ref "IC5") (pin "5") (pinfunction "SENSE_5") (pintype "passive"))
    )
    (net (code "130") (name "unconnected-(IC6-NC-Pad8)") (class "Default")
      (node (ref "IC6") (pin "8") (pinfunction "NC_8") (pintype "no_connect"))
    )
    (net (code "131") (name "unconnected-(IC6-REF-Pad1)") (class "Default")
      (node (ref "IC6") (pin "1") (pinfunction "REF_1") (pintype "passive"))
    )
    (net (code "132") (name "unconnected-(IC6-SENSE-Pad5)") (class "Default")
      (node (ref "IC6") (pin "5") (pinfunction "SENSE_5") (pintype "passive"))
    )
    (net (code "133") (name "unconnected-(IC9-NC-Pad4)") (class "Default")
      (node (ref "IC9") (pin "4") (pinfunction "NC_4") (pintype "input"))
    )
    (net (code "134") (name "unconnected-(IC9-NC-Pad5)") (class "Default")
      (node (ref "IC9") (pin "5") (pinfunction "NC_5") (pintype "input"))
    )
    (net (code "135") (name "unconnected-(IC9-NC-Pad11)") (class "Default")
      (node (ref "IC9") (pin "11") (pinfunction "NC_11") (pintype "input"))
    )
    (net (code "136") (name "unconnected-(IC9-NC-Pad14)") (class "Default")
      (node (ref "IC9") (pin "14") (pinfunction "NC_14") (pintype "input"))
    )
    (net (code "137") (name "unconnected-(IC10-NC-Pad4)") (class "Default")
      (node (ref "IC10") (pin "4") (pinfunction "NC_4") (pintype "input"))
    )
    (net (code "138") (name "unconnected-(IC10-NC-Pad5)") (class "Default")
      (node (ref "IC10") (pin "5") (pinfunction "NC_5") (pintype "input"))
    )
    (net (code "139") (name "unconnected-(IC10-NC-Pad11)") (class "Default")
      (node (ref "IC10") (pin "11") (pinfunction "NC_11") (pintype "input"))
    )
    (net (code "140") (name "unconnected-(IC10-NC-Pad14)") (class "Default")
      (node (ref "IC10") (pin "14") (pinfunction "NC_14") (pintype "input"))
    )
    (net (code "141") (name "unconnected-(IWIFI-Pad6)") (class "Default")
      (node (ref "IWIFI") (pin "6") (pinfunction "6_6") (pintype "passive"))
    )
    (net (code "142") (name "unconnected-(IWIFI-Pad8)") (class "Default")
      (node (ref "IWIFI") (pin "8") (pinfunction "8_8") (pintype "passive"))
    )
    (net (code "143") (name "unconnected-(IWIFI-Pad9)") (class "Default")
      (node (ref "IWIFI") (pin "9") (pinfunction "9_9") (pintype "passive"))
    )
    (net (code "144") (name "unconnected-(U1-NRST-Pad69)") (class "Default")
      (node (ref "U1") (pin "69") (pinfunction "NRST_69") (pintype "bidirectional"))
    )
    (net (code "145") (name "unconnected-(U1-PA2-Pad85)") (class "Default")
      (node (ref "U1") (pin "85") (pinfunction "PA2_85") (pintype "bidirectional"))
    )
    (net (code "146") (name "unconnected-(U1-PA3-Pad84)") (class "Default")
      (node (ref "U1") (pin "84") (pinfunction "PA3_84") (pintype "bidirectional"))
    )
    (net (code "147") (name "unconnected-(U1-PA4-Pad83)") (class "Default")
      (node (ref "U1") (pin "83") (pinfunction "PA4_83") (pintype "bidirectional"))
    )
    (net (code "148") (name "unconnected-(U1-PA5-Pad25)") (class "Default")
      (node (ref "U1") (pin "25") (pinfunction "PA5_25") (pintype "bidirectional"))
    )
    (net (code "149") (name "unconnected-(U1-PA6-Pad82)") (class "Default")
      (node (ref "U1") (pin "82") (pinfunction "PA6_82") (pintype "bidirectional"))
    )
    (net (code "150") (name "unconnected-(U1-PA7-Pad26)") (class "Default")
      (node (ref "U1") (pin "26") (pinfunction "PA7_26") (pintype "bidirectional"))
    )
    (net (code "151") (name "unconnected-(U1-PA8-Pad27)") (class "Default")
      (node (ref "U1") (pin "27") (pinfunction "PA8_27") (pintype "bidirectional"))
    )
    (net (code "152") (name "unconnected-(U1-PA9-Pad2)") (class "Default")
      (node (ref "U1") (pin "2") (pinfunction "PA9_2") (pintype "bidirectional"))
    )
    (net (code "153") (name "unconnected-(U1-PA10-Pad3)") (class "Default")
      (node (ref "U1") (pin "3") (pinfunction "PA10_3") (pintype "bidirectional"))
    )
    (net (code "154") (name "unconnected-(U1-PA14-Pad7)") (class "Default")
      (node (ref "U1") (pin "7") (pinfunction "PA14_7") (pintype "bidirectional"))
    )
    (net (code "155") (name "unconnected-(U1-PA15-Pad8)") (class "Default")
      (node (ref "U1") (pin "8") (pinfunction "PA15_8") (pintype "bidirectional"))
    )
    (net (code "156") (name "unconnected-(U1-PA17-Pad9)") (class "Default")
      (node (ref "U1") (pin "9") (pinfunction "PA17_9") (pintype "bidirectional"))
    )
    (net (code "157") (name "unconnected-(U1-PA18-Pad70)") (class "Default")
      (node (ref "U1") (pin "70") (pinfunction "PA18_70") (pintype "bidirectional"))
    )
    (net (code "158") (name "unconnected-(U1-PA20-Pad72)") (class "Default")
      (node (ref "U1") (pin "72") (pinfunction "PA20_72") (pintype "bidirectional"))
    )
    (net (code "159") (name "unconnected-(U1-PA21-Pad107)") (class "Default")
      (node (ref "U1") (pin "107") (pinfunction "PA21_107") (pintype "bidirectional"))
    )
    (net (code "160") (name "unconnected-(U1-PA25-Pad108)") (class "Default")
      (node (ref "U1") (pin "108") (pinfunction "PA25_108") (pintype "bidirectional"))
    )
    (net (code "161") (name "unconnected-(U1-PA26-Pad109)") (class "Default")
      (node (ref "U1") (pin "109") (pinfunction "PA26_109") (pintype "bidirectional"))
    )
    (net (code "162") (name "unconnected-(U1-PA27-Pad110)") (class "Default")
      (node (ref "U1") (pin "110") (pinfunction "PA27_110") (pintype "bidirectional"))
    )
    (net (code "163") (name "unconnected-(U1-PA28-Pad111)") (class "Default")
      (node (ref "U1") (pin "111") (pinfunction "PA28_111") (pintype "bidirectional"))
    )
    (net (code "164") (name "unconnected-(U1-PA29-Pad112)") (class "Default")
      (node (ref "U1") (pin "112") (pinfunction "PA29_112") (pintype "bidirectional"))
    )
    (net (code "165") (name "unconnected-(U1-PB0-Pad113)") (class "Default")
      (node (ref "U1") (pin "113") (pinfunction "PB0_113") (pintype "bidirectional"))
    )
    (net (code "166") (name "unconnected-(U1-PB1-Pad114)") (class "Default")
      (node (ref "U1") (pin "114") (pinfunction "PB1_114") (pintype "bidirectional"))
    )
    (net (code "167") (name "unconnected-(U1-PB2-Pad115)") (class "Default")
      (node (ref "U1") (pin "115") (pinfunction "PB2_115") (pintype "bidirectional"))
    )
    (net (code "168") (name "unconnected-(U1-PB3-Pad118)") (class "Default")
      (node (ref "U1") (pin "118") (pinfunction "PB3_118") (pintype "bidirectional"))
    )
    (net (code "169") (name "unconnected-(U1-PB4-Pad119)") (class "Default")
      (node (ref "U1") (pin "119") (pinfunction "PB4_119") (pintype "bidirectional"))
    )
    (net (code "170") (name "unconnected-(U1-PB5-Pad120)") (class "Default")
      (node (ref "U1") (pin "120") (pinfunction "PB5_120") (pintype "bidirectional"))
    )
    (net (code "171") (name "unconnected-(U1-PB6-Pad121)") (class "Default")
      (node (ref "U1") (pin "121") (pinfunction "PB6_121") (pintype "bidirectional"))
    )
    (net (code "172") (name "unconnected-(U1-PB7-Pad122)") (class "Default")
      (node (ref "U1") (pin "122") (pinfunction "PB7_122") (pintype "bidirectional"))
    )
    (net (code "173") (name "unconnected-(U1-PB8-Pad123)") (class "Default")
      (node (ref "U1") (pin "123") (pinfunction "PB8_123") (pintype "bidirectional"))
    )
    (net (code "174") (name "unconnected-(U1-PB9-Pad127)") (class "Default")
      (node (ref "U1") (pin "127") (pinfunction "PB9_127") (pintype "bidirectional"))
    )
    (net (code "175") (name "unconnected-(U1-PB10-Pad128)") (class "Default")
      (node (ref "U1") (pin "128") (pinfunction "PB10_128") (pintype "bidirectional"))
    )
    (net (code "176") (name "unconnected-(U1-PB11-Pad129)") (class "Default")
      (node (ref "U1") (pin "129") (pinfunction "PB11_129") (pintype "bidirectional"))
    )
    (net (code "177") (name "unconnected-(U1-PB16-Pad77)") (class "Default")
      (node (ref "U1") (pin "77") (pinfunction "PB16_77") (pintype "bidirectional"))
    )
    (net (code "178") (name "unconnected-(U1-PB17-Pad88)") (class "Default")
      (node (ref "U1") (pin "88") (pinfunction "PB17_88") (pintype "bidirectional"))
    )
    (net (code "179") (name "unconnected-(U1-PB18-Pad89)") (class "Default")
      (node (ref "U1") (pin "89") (pinfunction "PB18_89") (pintype "bidirectional"))
    )
    (net (code "180") (name "unconnected-(U1-PB19-Pad90)") (class "Default")
      (node (ref "U1") (pin "90") (pinfunction "PB19_90") (pintype "bidirectional"))
    )
    (net (code "181") (name "unconnected-(U1-PB20-Pad91)") (class "Default")
      (node (ref "U1") (pin "91") (pinfunction "PB20_91") (pintype "bidirectional"))
    )
    (net (code "182") (name "unconnected-(U1-PB21-Pad92)") (class "Default")
      (node (ref "U1") (pin "92") (pinfunction "PB21_92") (pintype "bidirectional"))
    )
    (net (code "183") (name "unconnected-(U1-PB22-Pad141)") (class "Default")
      (node (ref "U1") (pin "141") (pinfunction "PB22_141") (pintype "bidirectional"))
    )
    (net (code "184") (name "unconnected-(U1-PB23-Pad142)") (class "Default")
      (node (ref "U1") (pin "142") (pinfunction "PB23_142") (pintype "bidirectional"))
    )
    (net (code "185") (name "unconnected-(U1-PB24-Pad143)") (class "Default")
      (node (ref "U1") (pin "143") (pinfunction "PB24_143") (pintype "bidirectional"))
    )
    (net (code "186") (name "unconnected-(U1-PB26-Pad1)") (class "Default")
      (node (ref "U1") (pin "1") (pinfunction "PB26_1") (pintype "bidirectional"))
    )
    (net (code "187") (name "unconnected-(U1-PB28-Pad28)") (class "Default")
      (node (ref "U1") (pin "28") (pinfunction "PB28_28") (pintype "bidirectional"))
    )
    (net (code "188") (name "unconnected-(U1-PB29-Pad29)") (class "Default")
      (node (ref "U1") (pin "29") (pinfunction "PB29_29") (pintype "bidirectional"))
    )
    (net (code "189") (name "unconnected-(U1-PB30-Pad30)") (class "Default")
      (node (ref "U1") (pin "30") (pinfunction "PB30_30") (pintype "bidirectional"))
    )
    (net (code "190") (name "unconnected-(U1-PB31-Pad31)") (class "Default")
      (node (ref "U1") (pin "31") (pinfunction "PB31_31") (pintype "bidirectional"))
    )
    (net (code "191") (name "unconnected-(U1-PC1-Pad55)") (class "Default")
      (node (ref "U1") (pin "55") (pinfunction "PC1_55") (pintype "bidirectional"))
    )
    (net (code "192") (name "unconnected-(U1-PC2-Pad59)") (class "Default")
      (node (ref "U1") (pin "59") (pinfunction "PC2_59") (pintype "bidirectional"))
    )
    (net (code "193") (name "unconnected-(U1-PC3-Pad60)") (class "Default")
      (node (ref "U1") (pin "60") (pinfunction "PC3_60") (pintype "bidirectional"))
    )
    (net (code "194") (name "unconnected-(U1-PC4-Pad116)") (class "Default")
      (node (ref "U1") (pin "116") (pinfunction "PC4_116") (pintype "bidirectional"))
    )
    (net (code "195") (name "unconnected-(U1-PC5-Pad63)") (class "Default")
      (node (ref "U1") (pin "63") (pinfunction "PC5_63") (pintype "bidirectional"))
    )
    (net (code "196") (name "unconnected-(U1-PC6-Pad64)") (class "Default")
      (node (ref "U1") (pin "64") (pinfunction "PC6_64") (pintype "bidirectional"))
    )
    (net (code "197") (name "unconnected-(U1-PC7-Pad65)") (class "Default")
      (node (ref "U1") (pin "65") (pinfunction "PC7_65") (pintype "bidirectional"))
    )
    (net (code "198") (name "unconnected-(U1-PC8-Pad66)") (class "Default")
      (node (ref "U1") (pin "66") (pinfunction "PC8_66") (pintype "bidirectional"))
    )
    (net (code "199") (name "unconnected-(U1-PC9-Pad67)") (class "Default")
      (node (ref "U1") (pin "67") (pinfunction "PC9_67") (pintype "bidirectional"))
    )
    (net (code "200") (name "unconnected-(U1-PC10-Pad117)") (class "Default")
      (node (ref "U1") (pin "117") (pinfunction "PC10_117") (pintype "bidirectional"))
    )
    (net (code "201") (name "unconnected-(U1-PC11-Pad93)") (class "Default")
      (node (ref "U1") (pin "93") (pinfunction "PC11_93") (pintype "bidirectional"))
    )
    (net (code "202") (name "unconnected-(U1-PC16-Pad98)") (class "Default")
      (node (ref "U1") (pin "98") (pinfunction "PC16_98") (pintype "bidirectional"))
    )
    (net (code "203") (name "unconnected-(U1-PC17-Pad99)") (class "Default")
      (node (ref "U1") (pin "99") (pinfunction "PC17_99") (pintype "bidirectional"))
    )
    (net (code "204") (name "unconnected-(U1-PC18-Pad100)") (class "Default")
      (node (ref "U1") (pin "100") (pinfunction "PC18_100") (pintype "bidirectional"))
    )
    (net (code "205") (name "unconnected-(U1-PC19-Pad101)") (class "Default")
      (node (ref "U1") (pin "101") (pinfunction "PC19_101") (pintype "bidirectional"))
    )
    (net (code "206") (name "unconnected-(U1-PC20-Pad131)") (class "Default")
      (node (ref "U1") (pin "131") (pinfunction "PC20_131") (pintype "bidirectional"))
    )
    (net (code "207") (name "unconnected-(U1-PC27-Pad138)") (class "Default")
      (node (ref "U1") (pin "138") (pinfunction "PC27_138") (pintype "bidirectional"))
    )
    (net (code "208") (name "unconnected-(U1-PC29-Pad102)") (class "Default")
      (node (ref "U1") (pin "102") (pinfunction "PC29_102") (pintype "bidirectional"))
    )
    (net (code "209") (name "unconnected-(U1-PC30-Pad103)") (class "Default")
      (node (ref "U1") (pin "103") (pinfunction "PC30_103") (pintype "bidirectional"))
    )
    (net (code "210") (name "unconnected-(U1-PD0-Pad13)") (class "Default")
      (node (ref "U1") (pin "13") (pinfunction "PD0_13") (pintype "bidirectional"))
    )
    (net (code "211") (name "unconnected-(U1-PD1-Pad14)") (class "Default")
      (node (ref "U1") (pin "14") (pinfunction "PD1_14") (pintype "bidirectional"))
    )
    (net (code "212") (name "unconnected-(U1-PD2-Pad15)") (class "Default")
      (node (ref "U1") (pin "15") (pinfunction "PD2_15") (pintype "bidirectional"))
    )
    (net (code "213") (name "unconnected-(U1-PD3-Pad16)") (class "Default")
      (node (ref "U1") (pin "16") (pinfunction "PD3_16") (pintype "bidirectional"))
    )
    (net (code "214") (name "unconnected-(U1-PD4-Pad17)") (class "Default")
      (node (ref "U1") (pin "17") (pinfunction "PD4_17") (pintype "bidirectional"))
    )
    (net (code "215") (name "unconnected-(U1-PD5-Pad18)") (class "Default")
      (node (ref "U1") (pin "18") (pinfunction "PD5_18") (pintype "bidirectional"))
    )
    (net (code "216") (name "unconnected-(U1-PD6-Pad19)") (class "Default")
      (node (ref "U1") (pin "19") (pinfunction "PD6_19") (pintype "bidirectional"))
    )
    (net (code "217") (name "unconnected-(U1-PD7-Pad20)") (class "Default")
      (node (ref "U1") (pin "20") (pinfunction "PD7_20") (pintype "bidirectional"))
    )
    (net (code "218") (name "unconnected-(U1-PD8-Pad21)") (class "Default")
      (node (ref "U1") (pin "21") (pinfunction "PD8_21") (pintype "bidirectional"))
    )
    (net (code "219") (name "unconnected-(U1-PD9-Pad22)") (class "Default")
      (node (ref "U1") (pin "22") (pinfunction "PD9_22") (pintype "bidirectional"))
    )
    (net (code "220") (name "unconnected-(U1-PD10-Pad32)") (class "Default")
      (node (ref "U1") (pin "32") (pinfunction "PD10_32") (pintype "bidirectional"))
    )
    (net (code "221") (name "unconnected-(U1-SHDN-Pad50)") (class "Default")
      (node (ref "U1") (pin "50") (pinfunction "SHDN_50") (pintype "output"))
    )
    (net (code "222") (name "unconnected-(U1-TST-Pad51)") (class "Default")
      (node (ref "U1") (pin "51") (pinfunction "TST_51") (pintype "input"))
    )
    (net (code "223") (name "unconnected-(U7-WC-PadPIN7)") (class "Default")
      (node (ref "U7") (pin "PIN7") (pinfunction "WC_PIN7") (pintype "bidirectional"))
    )
    (net (code "224") (name "unconnected-(X1-PadS1)") (class "Default")
      (node (ref "X1") (pin "S1") (pinfunction "S1_S1") (pintype "passive"))
    )
    (net (code "225") (name "unconnected-(X1-PadS2)") (class "Default")
      (node (ref "X1") (pin "S2") (pinfunction "S2_S2") (pintype "passive"))
    )
  )
)
